# Slave.net
KiCad netlist of a schematic drawn in Altium Designer
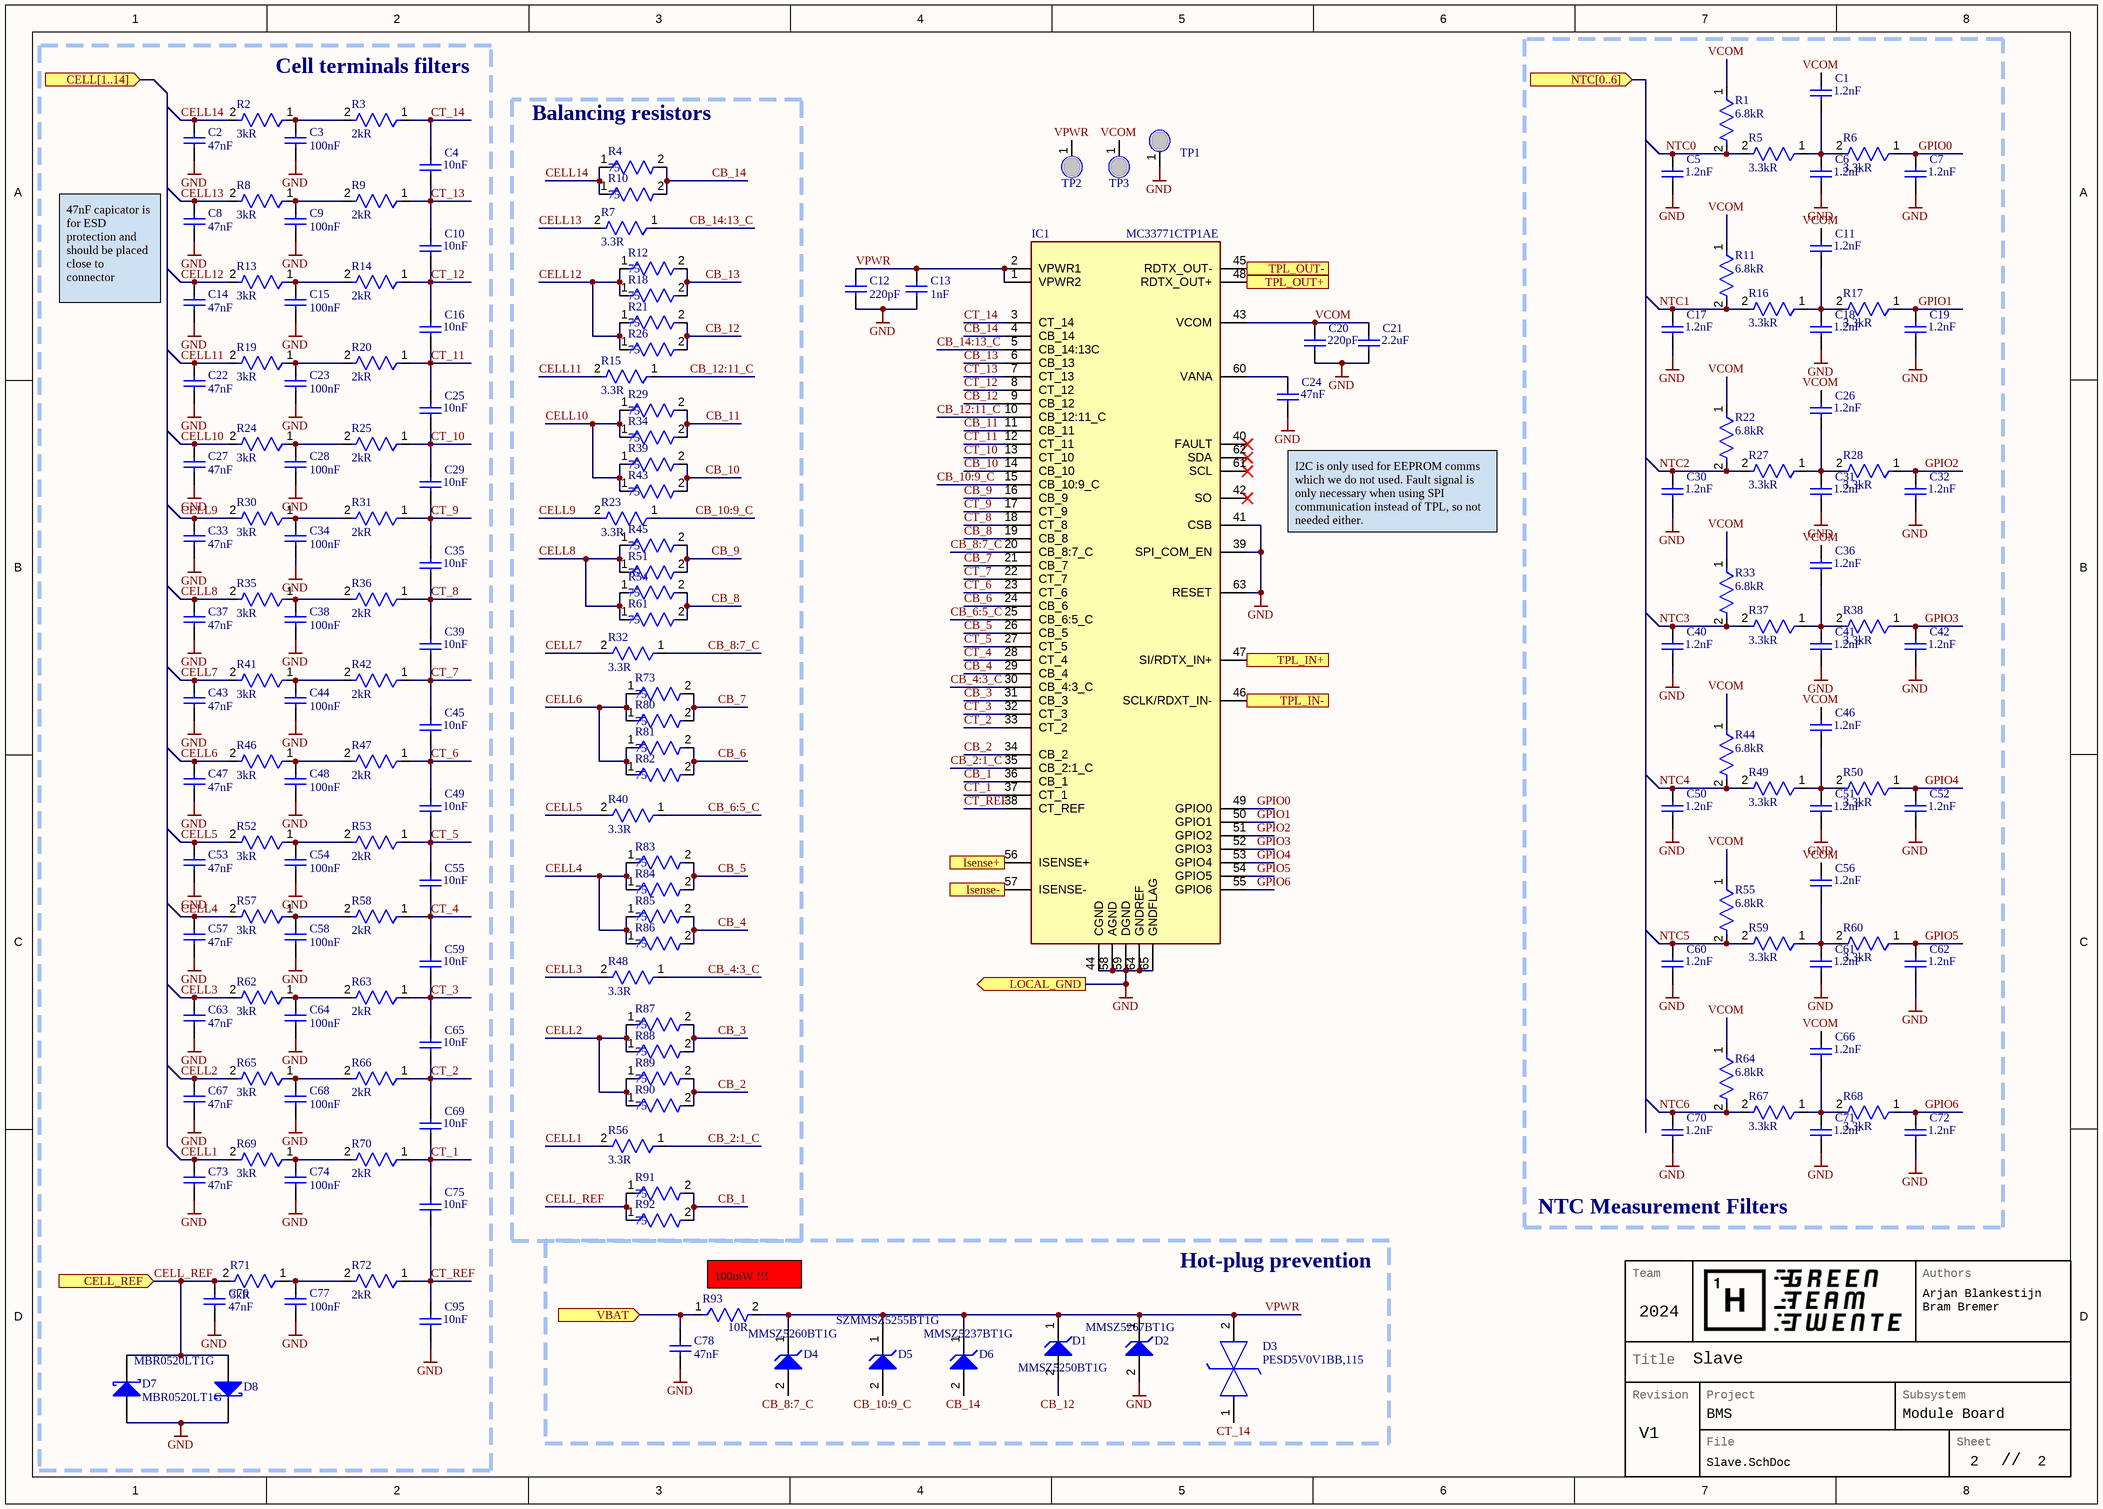
[diagram p0: Slave.SchDoc]

(export (version "E")
  (design (tool "Eeschema 10.0.6"))
  (components
    (comp (ref "C1")
      (value "1.2nF")
      (footprint "WCAP-CSGP_0402_L1W0.5H0.5")
      (description "GTT Standard 0402 non-polarized capacitor")
      (fields (field (name "Comment") "CAP 0402 1.2nF X7R"))
      (libsource (lib "Green Team Twente") (part "CAP_NONPOL_GENERIC"))
    )
    (comp (ref "C2")
      (value "47nF")
      (footprint "WCAP-CSGP_0603_L1.6W0.8H0.8_Reflow")
      (description "GTT Standard 0603 non-polarized capacitor")
      (fields (field (name "TOLERANCE") "5%") (field (name "Comment") "CAP 0603 47nF X7R"))
      (libsource (lib "Green Team Twente") (part "CAP_NONPOL_GENERIC"))
    )
    (comp (ref "C3")
      (value "100nF")
      (footprint "WCAP-CSGP_0603_L1.6W0.8H0.8_Reflow")
      (description "GTT Standard 0603 non-polarized capacitor")
      (fields (field (name "TOLERANCE") "5%") (field (name "Comment") "CAP 0603 100nF X7R"))
      (libsource (lib "Green Team Twente") (part "CAP_NONPOL_GENERIC"))
    )
    (comp (ref "C4")
      (value "10nF")
      (footprint "WCAP-CSGP_0402_L1W0.5H0.5")
      (description "GTT Standard 0402 non-polarized capacitor")
      (fields (field (name "Comment") "CAP 0402 10nF X7R"))
      (libsource (lib "Green Team Twente") (part "CAP_NONPOL_GENERIC"))
    )
    (comp (ref "C5")
      (value "1.2nF")
      (footprint "WCAP-CSGP_0402_L1W0.5H0.5")
      (description "GTT Standard 0402 non-polarized capacitor")
      (fields (field (name "Comment") "CAP 0402 1.2nF X7R"))
      (libsource (lib "Green Team Twente") (part "CAP_NONPOL_GENERIC"))
    )
    (comp (ref "C6")
      (value "1.2nF")
      (footprint "WCAP-CSGP_0402_L1W0.5H0.5")
      (description "GTT Standard 0402 non-polarized capacitor")
      (fields (field (name "Comment") "CAP 0402 1.2nF X7R"))
      (libsource (lib "Green Team Twente") (part "CAP_NONPOL_GENERIC"))
    )
    (comp (ref "C7")
      (value "1.2nF")
      (footprint "WCAP-CSGP_0402_L1W0.5H0.5")
      (description "GTT Standard 0402 non-polarized capacitor")
      (fields (field (name "Comment") "CAP 0402 1.2nF X7R"))
      (libsource (lib "Green Team Twente") (part "CAP_NONPOL_GENERIC"))
    )
    (comp (ref "C8")
      (value "47nF")
      (footprint "WCAP-CSGP_0603_L1.6W0.8H0.8_Reflow")
      (description "GTT Standard 0603 non-polarized capacitor")
      (fields (field (name "TOLERANCE") "5%") (field (name "Comment") "CAP 0603 47nF X7R"))
      (libsource (lib "Green Team Twente") (part "CAP_NONPOL_GENERIC"))
    )
    (comp (ref "C9")
      (value "100nF")
      (footprint "WCAP-CSGP_0603_L1.6W0.8H0.8_Reflow")
      (description "GTT Standard 0603 non-polarized capacitor")
      (fields (field (name "TOLERANCE") "5%") (field (name "Comment") "CAP 0603 100nF X7R"))
      (libsource (lib "Green Team Twente") (part "CAP_NONPOL_GENERIC"))
    )
    (comp (ref "C10")
      (value "10nF")
      (footprint "WCAP-CSGP_0402_L1W0.5H0.5")
      (description "GTT Standard 0402 non-polarized capacitor")
      (fields (field (name "Comment") "CAP 0402 10nF X7R"))
      (libsource (lib "Green Team Twente") (part "CAP_NONPOL_GENERIC"))
    )
    (comp (ref "C11")
      (value "1.2nF")
      (footprint "WCAP-CSGP_0402_L1W0.5H0.5")
      (description "GTT Standard 0402 non-polarized capacitor")
      (fields (field (name "Comment") "CAP 0402 1.2nF X7R"))
      (libsource (lib "Green Team Twente") (part "CAP_NONPOL_GENERIC"))
    )
    (comp (ref "C12")
      (value "220pF")
      (footprint "WCAP-CSGP_0603_L1.6W0.8H0.8_Reflow")
      (description "GTT Standard 0603 non-polarized capacitor")
      (fields (field (name "TOLERANCE") "5%") (field (name "Comment") "CAP 0603 220pF X7R"))
      (libsource (lib "Green Team Twente") (part "CAP_NONPOL_GENERIC"))
    )
    (comp (ref "C13")
      (value "1nF")
      (footprint "WCAP-CSGP_0603_L1.6W0.8H0.8_Reflow")
      (description "GTT Standard 0603 non-polarized capacitor")
      (fields (field (name "TOLERANCE") "5%") (field (name "Comment") "CAP 0603 1nF X7R"))
      (libsource (lib "Green Team Twente") (part "CAP_NONPOL_GENERIC"))
    )
    (comp (ref "C14")
      (value "47nF")
      (footprint "WCAP-CSGP_0603_L1.6W0.8H0.8_Reflow")
      (description "GTT Standard 0603 non-polarized capacitor")
      (fields (field (name "TOLERANCE") "5%") (field (name "Comment") "CAP 0603 47nF X7R"))
      (libsource (lib "Green Team Twente") (part "CAP_NONPOL_GENERIC"))
    )
    (comp (ref "C15")
      (value "100nF")
      (footprint "WCAP-CSGP_0603_L1.6W0.8H0.8_Reflow")
      (description "GTT Standard 0603 non-polarized capacitor")
      (fields (field (name "TOLERANCE") "5%") (field (name "Comment") "CAP 0603 100nF X7R"))
      (libsource (lib "Green Team Twente") (part "CAP_NONPOL_GENERIC"))
    )
    (comp (ref "C16")
      (value "10nF")
      (footprint "WCAP-CSGP_0402_L1W0.5H0.5")
      (description "GTT Standard 0402 non-polarized capacitor")
      (fields (field (name "Comment") "CAP 0402 10nF X7R"))
      (libsource (lib "Green Team Twente") (part "CAP_NONPOL_GENERIC"))
    )
    (comp (ref "C17")
      (value "1.2nF")
      (footprint "WCAP-CSGP_0402_L1W0.5H0.5")
      (description "GTT Standard 0402 non-polarized capacitor")
      (fields (field (name "Comment") "CAP 0402 1.2nF X7R"))
      (libsource (lib "Green Team Twente") (part "CAP_NONPOL_GENERIC"))
    )
    (comp (ref "C18")
      (value "1.2nF")
      (footprint "WCAP-CSGP_0402_L1W0.5H0.5")
      (description "GTT Standard 0402 non-polarized capacitor")
      (fields (field (name "Comment") "CAP 0402 1.2nF X7R"))
      (libsource (lib "Green Team Twente") (part "CAP_NONPOL_GENERIC"))
    )
    (comp (ref "C19")
      (value "1.2nF")
      (footprint "WCAP-CSGP_0402_L1W0.5H0.5")
      (description "GTT Standard 0402 non-polarized capacitor")
      (fields (field (name "Comment") "CAP 0402 1.2nF X7R"))
      (libsource (lib "Green Team Twente") (part "CAP_NONPOL_GENERIC"))
    )
    (comp (ref "C20")
      (value "220pF")
      (footprint "WCAP-CSGP_0402_L1W0.5H0.5")
      (description "GTT Standard 0402 non-polarized capacitor")
      (fields (field (name "Comment") "CAP 0402 220pF X7R"))
      (libsource (lib "Green Team Twente") (part "CAP_NONPOL_GENERIC"))
    )
    (comp (ref "C21")
      (value "2.2uF")
      (footprint "WCAP-CSGP_0402_L1W0.5H0.5")
      (description "GTT Standard 0402 non-polarized capacitor")
      (fields (field (name "Comment") "CAP 0402 2.2uF X7R"))
      (libsource (lib "Green Team Twente") (part "CAP_NONPOL_GENERIC"))
    )
    (comp (ref "C22")
      (value "47nF")
      (footprint "WCAP-CSGP_0603_L1.6W0.8H0.8_Reflow")
      (description "GTT Standard 0603 non-polarized capacitor")
      (fields (field (name "TOLERANCE") "5%") (field (name "Comment") "CAP 0603 47nF X7R"))
      (libsource (lib "Green Team Twente") (part "CAP_NONPOL_GENERIC"))
    )
    (comp (ref "C23")
      (value "100nF")
      (footprint "WCAP-CSGP_0603_L1.6W0.8H0.8_Reflow")
      (description "GTT Standard 0603 non-polarized capacitor")
      (fields (field (name "TOLERANCE") "5%") (field (name "Comment") "CAP 0603 100nF X7R"))
      (libsource (lib "Green Team Twente") (part "CAP_NONPOL_GENERIC"))
    )
    (comp (ref "C24")
      (value "47nF")
      (footprint "WCAP-CSGP_0402_L1W0.5H0.5")
      (description "GTT Standard 0402 non-polarized capacitor")
      (fields (field (name "Comment") "CAP 0402 47nF X7R"))
      (libsource (lib "Green Team Twente") (part "CAP_NONPOL_GENERIC"))
    )
    (comp (ref "C25")
      (value "10nF")
      (footprint "WCAP-CSGP_0402_L1W0.5H0.5")
      (description "GTT Standard 0402 non-polarized capacitor")
      (fields (field (name "Comment") "CAP 0402 10nF X7R"))
      (libsource (lib "Green Team Twente") (part "CAP_NONPOL_GENERIC"))
    )
    (comp (ref "C26")
      (value "1.2nF")
      (footprint "WCAP-CSGP_0402_L1W0.5H0.5")
      (description "GTT Standard 0402 non-polarized capacitor")
      (fields (field (name "Comment") "CAP 0402 1.2nF X7R"))
      (libsource (lib "Green Team Twente") (part "CAP_NONPOL_GENERIC"))
    )
    (comp (ref "C27")
      (value "47nF")
      (footprint "WCAP-CSGP_0603_L1.6W0.8H0.8_Reflow")
      (description "GTT Standard 0603 non-polarized capacitor")
      (fields (field (name "TOLERANCE") "5%") (field (name "Comment") "CAP 0603 47nF X7R"))
      (libsource (lib "Green Team Twente") (part "CAP_NONPOL_GENERIC"))
    )
    (comp (ref "C28")
      (value "100nF")
      (footprint "WCAP-CSGP_0603_L1.6W0.8H0.8_Reflow")
      (description "GTT Standard 0603 non-polarized capacitor")
      (fields (field (name "TOLERANCE") "5%") (field (name "Comment") "CAP 0603 100nF X7R"))
      (libsource (lib "Green Team Twente") (part "CAP_NONPOL_GENERIC"))
    )
    (comp (ref "C29")
      (value "10nF")
      (footprint "WCAP-CSGP_0402_L1W0.5H0.5")
      (description "GTT Standard 0402 non-polarized capacitor")
      (fields (field (name "Comment") "CAP 0402 10nF X7R"))
      (libsource (lib "Green Team Twente") (part "CAP_NONPOL_GENERIC"))
    )
    (comp (ref "C30")
      (value "1.2nF")
      (footprint "WCAP-CSGP_0402_L1W0.5H0.5")
      (description "GTT Standard 0402 non-polarized capacitor")
      (fields (field (name "Comment") "CAP 0402 1.2nF X7R"))
      (libsource (lib "Green Team Twente") (part "CAP_NONPOL_GENERIC"))
    )
    (comp (ref "C31")
      (value "1.2nF")
      (footprint "WCAP-CSGP_0402_L1W0.5H0.5")
      (description "GTT Standard 0402 non-polarized capacitor")
      (fields (field (name "Comment") "CAP 0402 1.2nF X7R"))
      (libsource (lib "Green Team Twente") (part "CAP_NONPOL_GENERIC"))
    )
    (comp (ref "C32")
      (value "1.2nF")
      (footprint "WCAP-CSGP_0402_L1W0.5H0.5")
      (description "GTT Standard 0402 non-polarized capacitor")
      (fields (field (name "Comment") "CAP 0402 1.2nF X7R"))
      (libsource (lib "Green Team Twente") (part "CAP_NONPOL_GENERIC"))
    )
    (comp (ref "C33")
      (value "47nF")
      (footprint "WCAP-CSGP_0603_L1.6W0.8H0.8_Reflow")
      (description "GTT Standard 0603 non-polarized capacitor")
      (fields (field (name "TOLERANCE") "5%") (field (name "Comment") "CAP 0603 47nF X7R"))
      (libsource (lib "Green Team Twente") (part "CAP_NONPOL_GENERIC"))
    )
    (comp (ref "C34")
      (value "100nF")
      (footprint "WCAP-CSGP_0603_L1.6W0.8H0.8_Reflow")
      (description "GTT Standard 0603 non-polarized capacitor")
      (fields (field (name "TOLERANCE") "5%") (field (name "Comment") "CAP 0603 100nF X7R"))
      (libsource (lib "Green Team Twente") (part "CAP_NONPOL_GENERIC"))
    )
    (comp (ref "C35")
      (value "10nF")
      (footprint "WCAP-CSGP_0402_L1W0.5H0.5")
      (description "GTT Standard 0402 non-polarized capacitor")
      (fields (field (name "Comment") "CAP 0402 10nF X7R"))
      (libsource (lib "Green Team Twente") (part "CAP_NONPOL_GENERIC"))
    )
    (comp (ref "C36")
      (value "1.2nF")
      (footprint "WCAP-CSGP_0402_L1W0.5H0.5")
      (description "GTT Standard 0402 non-polarized capacitor")
      (fields (field (name "Comment") "CAP 0402 1.2nF X7R"))
      (libsource (lib "Green Team Twente") (part "CAP_NONPOL_GENERIC"))
    )
    (comp (ref "C37")
      (value "47nF")
      (footprint "WCAP-CSGP_0603_L1.6W0.8H0.8_Reflow")
      (description "GTT Standard 0603 non-polarized capacitor")
      (fields (field (name "TOLERANCE") "5%") (field (name "Comment") "CAP 0603 47nF X7R"))
      (libsource (lib "Green Team Twente") (part "CAP_NONPOL_GENERIC"))
    )
    (comp (ref "C38")
      (value "100nF")
      (footprint "WCAP-CSGP_0603_L1.6W0.8H0.8_Reflow")
      (description "GTT Standard 0603 non-polarized capacitor")
      (fields (field (name "TOLERANCE") "5%") (field (name "Comment") "CAP 0603 100nF X7R"))
      (libsource (lib "Green Team Twente") (part "CAP_NONPOL_GENERIC"))
    )
    (comp (ref "C39")
      (value "10nF")
      (footprint "WCAP-CSGP_0402_L1W0.5H0.5")
      (description "GTT Standard 0402 non-polarized capacitor")
      (fields (field (name "Comment") "CAP 0402 10nF X7R"))
      (libsource (lib "Green Team Twente") (part "CAP_NONPOL_GENERIC"))
    )
    (comp (ref "C40")
      (value "1.2nF")
      (footprint "WCAP-CSGP_0402_L1W0.5H0.5")
      (description "GTT Standard 0402 non-polarized capacitor")
      (fields (field (name "Comment") "CAP 0402 1.2nF X7R"))
      (libsource (lib "Green Team Twente") (part "CAP_NONPOL_GENERIC"))
    )
    (comp (ref "C41")
      (value "1.2nF")
      (footprint "WCAP-CSGP_0402_L1W0.5H0.5")
      (description "GTT Standard 0402 non-polarized capacitor")
      (fields (field (name "Comment") "CAP 0402 1.2nF X7R"))
      (libsource (lib "Green Team Twente") (part "CAP_NONPOL_GENERIC"))
    )
    (comp (ref "C42")
      (value "1.2nF")
      (footprint "WCAP-CSGP_0402_L1W0.5H0.5")
      (description "GTT Standard 0402 non-polarized capacitor")
      (fields (field (name "Comment") "CAP 0402 1.2nF X7R"))
      (libsource (lib "Green Team Twente") (part "CAP_NONPOL_GENERIC"))
    )
    (comp (ref "C43")
      (value "47nF")
      (footprint "WCAP-CSGP_0603_L1.6W0.8H0.8_Reflow")
      (description "GTT Standard 0603 non-polarized capacitor")
      (fields (field (name "TOLERANCE") "5%") (field (name "Comment") "CAP 0603 47nF X7R"))
      (libsource (lib "Green Team Twente") (part "CAP_NONPOL_GENERIC"))
    )
    (comp (ref "C44")
      (value "100nF")
      (footprint "WCAP-CSGP_0603_L1.6W0.8H0.8_Reflow")
      (description "GTT Standard 0603 non-polarized capacitor")
      (fields (field (name "TOLERANCE") "5%") (field (name "Comment") "CAP 0603 100nF X7R"))
      (libsource (lib "Green Team Twente") (part "CAP_NONPOL_GENERIC"))
    )
    (comp (ref "C45")
      (value "10nF")
      (footprint "WCAP-CSGP_0402_L1W0.5H0.5")
      (description "GTT Standard 0402 non-polarized capacitor")
      (fields (field (name "Comment") "CAP 0402 10nF X7R"))
      (libsource (lib "Green Team Twente") (part "CAP_NONPOL_GENERIC"))
    )
    (comp (ref "C46")
      (value "1.2nF")
      (footprint "WCAP-CSGP_0402_L1W0.5H0.5")
      (description "GTT Standard 0402 non-polarized capacitor")
      (fields (field (name "Comment") "CAP 0402 1.2nF X7R"))
      (libsource (lib "Green Team Twente") (part "CAP_NONPOL_GENERIC"))
    )
    (comp (ref "C47")
      (value "47nF")
      (footprint "WCAP-CSGP_0603_L1.6W0.8H0.8_Reflow")
      (description "GTT Standard 0603 non-polarized capacitor")
      (fields (field (name "TOLERANCE") "5%") (field (name "Comment") "CAP 0603 47nF X7R"))
      (libsource (lib "Green Team Twente") (part "CAP_NONPOL_GENERIC"))
    )
    (comp (ref "C48")
      (value "100nF")
      (footprint "WCAP-CSGP_0603_L1.6W0.8H0.8_Reflow")
      (description "GTT Standard 0603 non-polarized capacitor")
      (fields (field (name "TOLERANCE") "5%") (field (name "Comment") "CAP 0603 100nF X7R"))
      (libsource (lib "Green Team Twente") (part "CAP_NONPOL_GENERIC"))
    )
    (comp (ref "C49")
      (value "10nF")
      (footprint "WCAP-CSGP_0402_L1W0.5H0.5")
      (description "GTT Standard 0402 non-polarized capacitor")
      (fields (field (name "Comment") "CAP 0402 10nF X7R"))
      (libsource (lib "Green Team Twente") (part "CAP_NONPOL_GENERIC"))
    )
    (comp (ref "C50")
      (value "1.2nF")
      (footprint "WCAP-CSGP_0402_L1W0.5H0.5")
      (description "GTT Standard 0402 non-polarized capacitor")
      (fields (field (name "Comment") "CAP 0402 1.2nF X7R"))
      (libsource (lib "Green Team Twente") (part "CAP_NONPOL_GENERIC"))
    )
    (comp (ref "C51")
      (value "1.2nF")
      (footprint "WCAP-CSGP_0402_L1W0.5H0.5")
      (description "GTT Standard 0402 non-polarized capacitor")
      (fields (field (name "Comment") "CAP 0402 1.2nF X7R"))
      (libsource (lib "Green Team Twente") (part "CAP_NONPOL_GENERIC"))
    )
    (comp (ref "C52")
      (value "1.2nF")
      (footprint "WCAP-CSGP_0402_L1W0.5H0.5")
      (description "GTT Standard 0402 non-polarized capacitor")
      (fields (field (name "Comment") "CAP 0402 1.2nF X7R"))
      (libsource (lib "Green Team Twente") (part "CAP_NONPOL_GENERIC"))
    )
    (comp (ref "C53")
      (value "47nF")
      (footprint "WCAP-CSGP_0603_L1.6W0.8H0.8_Reflow")
      (description "GTT Standard 0603 non-polarized capacitor")
      (fields (field (name "TOLERANCE") "5%") (field (name "Comment") "CAP 0603 47nF X7R"))
      (libsource (lib "Green Team Twente") (part "CAP_NONPOL_GENERIC"))
    )
    (comp (ref "C54")
      (value "100nF")
      (footprint "WCAP-CSGP_0603_L1.6W0.8H0.8_Reflow")
      (description "GTT Standard 0603 non-polarized capacitor")
      (fields (field (name "TOLERANCE") "5%") (field (name "Comment") "CAP 0603 100nF X7R"))
      (libsource (lib "Green Team Twente") (part "CAP_NONPOL_GENERIC"))
    )
    (comp (ref "C55")
      (value "10nF")
      (footprint "WCAP-CSGP_0402_L1W0.5H0.5")
      (description "GTT Standard 0402 non-polarized capacitor")
      (fields (field (name "Comment") "CAP 0402 10nF X7R"))
      (libsource (lib "Green Team Twente") (part "CAP_NONPOL_GENERIC"))
    )
    (comp (ref "C56")
      (value "1.2nF")
      (footprint "WCAP-CSGP_0402_L1W0.5H0.5")
      (description "GTT Standard 0402 non-polarized capacitor")
      (fields (field (name "Comment") "CAP 0402 1.2nF X7R"))
      (libsource (lib "Green Team Twente") (part "CAP_NONPOL_GENERIC"))
    )
    (comp (ref "C57")
      (value "47nF")
      (footprint "WCAP-CSGP_0603_L1.6W0.8H0.8_Reflow")
      (description "GTT Standard 0603 non-polarized capacitor")
      (fields (field (name "TOLERANCE") "5%") (field (name "Comment") "CAP 0603 47nF X7R"))
      (libsource (lib "Green Team Twente") (part "CAP_NONPOL_GENERIC"))
    )
    (comp (ref "C58")
      (value "100nF")
      (footprint "WCAP-CSGP_0603_L1.6W0.8H0.8_Reflow")
      (description "GTT Standard 0603 non-polarized capacitor")
      (fields (field (name "TOLERANCE") "5%") (field (name "Comment") "CAP 0603 100nF X7R"))
      (libsource (lib "Green Team Twente") (part "CAP_NONPOL_GENERIC"))
    )
    (comp (ref "C59")
      (value "10nF")
      (footprint "WCAP-CSGP_0402_L1W0.5H0.5")
      (description "GTT Standard 0402 non-polarized capacitor")
      (fields (field (name "Comment") "CAP 0402 10nF X7R"))
      (libsource (lib "Green Team Twente") (part "CAP_NONPOL_GENERIC"))
    )
    (comp (ref "C60")
      (value "1.2nF")
      (footprint "WCAP-CSGP_0402_L1W0.5H0.5")
      (description "GTT Standard 0402 non-polarized capacitor")
      (fields (field (name "Comment") "CAP 0402 1.2nF X7R"))
      (libsource (lib "Green Team Twente") (part "CAP_NONPOL_GENERIC"))
    )
    (comp (ref "C61")
      (value "1.2nF")
      (footprint "WCAP-CSGP_0402_L1W0.5H0.5")
      (description "GTT Standard 0402 non-polarized capacitor")
      (fields (field (name "Comment") "CAP 0402 1.2nF X7R"))
      (libsource (lib "Green Team Twente") (part "CAP_NONPOL_GENERIC"))
    )
    (comp (ref "C62")
      (value "1.2nF")
      (footprint "WCAP-CSGP_0402_L1W0.5H0.5")
      (description "GTT Standard 0402 non-polarized capacitor")
      (fields (field (name "Comment") "CAP 0402 1.2nF X7R"))
      (libsource (lib "Green Team Twente") (part "CAP_NONPOL_GENERIC"))
    )
    (comp (ref "C63")
      (value "47nF")
      (footprint "WCAP-CSGP_0603_L1.6W0.8H0.8_Reflow")
      (description "GTT Standard 0603 non-polarized capacitor")
      (fields (field (name "TOLERANCE") "5%") (field (name "Comment") "CAP 0603 47nF X7R"))
      (libsource (lib "Green Team Twente") (part "CAP_NONPOL_GENERIC"))
    )
    (comp (ref "C64")
      (value "100nF")
      (footprint "WCAP-CSGP_0603_L1.6W0.8H0.8_Reflow")
      (description "GTT Standard 0603 non-polarized capacitor")
      (fields (field (name "TOLERANCE") "5%") (field (name "Comment") "CAP 0603 100nF X7R"))
      (libsource (lib "Green Team Twente") (part "CAP_NONPOL_GENERIC"))
    )
    (comp (ref "C65")
      (value "10nF")
      (footprint "WCAP-CSGP_0402_L1W0.5H0.5")
      (description "GTT Standard 0402 non-polarized capacitor")
      (fields (field (name "Comment") "CAP 0402 10nF X7R"))
      (libsource (lib "Green Team Twente") (part "CAP_NONPOL_GENERIC"))
    )
    (comp (ref "C66")
      (value "1.2nF")
      (footprint "WCAP-CSGP_0402_L1W0.5H0.5")
      (description "GTT Standard 0402 non-polarized capacitor")
      (fields (field (name "Comment") "CAP 0402 1.2nF X7R"))
      (libsource (lib "Green Team Twente") (part "CAP_NONPOL_GENERIC"))
    )
    (comp (ref "C67")
      (value "47nF")
      (footprint "WCAP-CSGP_0603_L1.6W0.8H0.8_Reflow")
      (description "GTT Standard 0603 non-polarized capacitor")
      (fields (field (name "TOLERANCE") "5%") (field (name "Comment") "CAP 0603 47nF X7R"))
      (libsource (lib "Green Team Twente") (part "CAP_NONPOL_GENERIC"))
    )
    (comp (ref "C68")
      (value "100nF")
      (footprint "WCAP-CSGP_0603_L1.6W0.8H0.8_Reflow")
      (description "GTT Standard 0603 non-polarized capacitor")
      (fields (field (name "TOLERANCE") "5%") (field (name "Comment") "CAP 0603 100nF X7R"))
      (libsource (lib "Green Team Twente") (part "CAP_NONPOL_GENERIC"))
    )
    (comp (ref "C69")
      (value "10nF")
      (footprint "WCAP-CSGP_0402_L1W0.5H0.5")
      (description "GTT Standard 0402 non-polarized capacitor")
      (fields (field (name "Comment") "CAP 0402 10nF X7R"))
      (libsource (lib "Green Team Twente") (part "CAP_NONPOL_GENERIC"))
    )
    (comp (ref "C70")
      (value "1.2nF")
      (footprint "WCAP-CSGP_0402_L1W0.5H0.5")
      (description "GTT Standard 0402 non-polarized capacitor")
      (fields (field (name "Comment") "CAP 0402 1.2nF X7R"))
      (libsource (lib "Green Team Twente") (part "CAP_NONPOL_GENERIC"))
    )
    (comp (ref "C71")
      (value "1.2nF")
      (footprint "WCAP-CSGP_0402_L1W0.5H0.5")
      (description "GTT Standard 0402 non-polarized capacitor")
      (fields (field (name "Comment") "CAP 0402 1.2nF X7R"))
      (libsource (lib "Green Team Twente") (part "CAP_NONPOL_GENERIC"))
    )
    (comp (ref "C72")
      (value "1.2nF")
      (footprint "WCAP-CSGP_0402_L1W0.5H0.5")
      (description "GTT Standard 0402 non-polarized capacitor")
      (fields (field (name "Comment") "CAP 0402 1.2nF X7R"))
      (libsource (lib "Green Team Twente") (part "CAP_NONPOL_GENERIC"))
    )
    (comp (ref "C73")
      (value "47nF")
      (footprint "WCAP-CSGP_0603_L1.6W0.8H0.8_Reflow")
      (description "GTT Standard 0603 non-polarized capacitor")
      (fields (field (name "TOLERANCE") "5%") (field (name "Comment") "CAP 0603 47nF X7R"))
      (libsource (lib "Green Team Twente") (part "CAP_NONPOL_GENERIC"))
    )
    (comp (ref "C74")
      (value "100nF")
      (footprint "WCAP-CSGP_0603_L1.6W0.8H0.8_Reflow")
      (description "GTT Standard 0603 non-polarized capacitor")
      (fields (field (name "TOLERANCE") "5%") (field (name "Comment") "CAP 0603 100nF X7R"))
      (libsource (lib "Green Team Twente") (part "CAP_NONPOL_GENERIC"))
    )
    (comp (ref "C75")
      (value "10nF")
      (footprint "WCAP-CSGP_0402_L1W0.5H0.5")
      (description "GTT Standard 0402 non-polarized capacitor")
      (fields (field (name "Comment") "CAP 0402 10nF X7R"))
      (libsource (lib "Green Team Twente") (part "CAP_NONPOL_GENERIC"))
    )
    (comp (ref "C76")
      (value "47nF")
      (footprint "WCAP-CSGP_0603_L1.6W0.8H0.8_Reflow")
      (description "GTT Standard 0603 non-polarized capacitor")
      (fields (field (name "TOLERANCE") "5%") (field (name "Comment") "CAP 0603 47nF X7R"))
      (libsource (lib "Green Team Twente") (part "CAP_NONPOL_GENERIC"))
    )
    (comp (ref "C77")
      (value "100nF")
      (footprint "WCAP-CSGP_0603_L1.6W0.8H0.8_Reflow")
      (description "GTT Standard 0603 non-polarized capacitor")
      (fields (field (name "TOLERANCE") "5%") (field (name "Comment") "CAP 0603 100nF X7R"))
      (libsource (lib "Green Team Twente") (part "CAP_NONPOL_GENERIC"))
    )
    (comp (ref "C78")
      (value "47nF")
      (footprint "WCAP-CSGP_0603_L1.6W0.8H0.8_Reflow")
      (description "GTT Standard 0603 non-polarized capacitor")
      (fields (field (name "TOLERANCE") "5%") (field (name "Comment") "CAP 0603 47nF X7R"))
      (libsource (lib "Green Team Twente") (part "CAP_NONPOL_GENERIC"))
    )
    (comp (ref "C95")
      (value "10nF")
      (footprint "WCAP-CSGP_0402_L1W0.5H0.5")
      (description "GTT Standard 0402 non-polarized capacitor")
      (fields (field (name "Comment") "CAP 0402 10nF X7R"))
      (libsource (lib "Green Team Twente") (part "CAP_NONPOL_GENERIC"))
    )
    (comp (ref "D1")
      (value "MMSZ5250BT1G")
      (footprint "ONSC-SOD-123-2-425-04_V")
      (description "Zener Voltage Regulator, 500 mW, 2-Pin SOD-123, Pb-Free, Tape and Reel")
      (fields (field (name "MANUFACTURER") "On Semiconductor"))
      (libsource (lib "Altium Content Vault") (part "ONSC-K1A2-2"))
    )
    (comp (ref "D2")
      (value "MMSZ5267BT1G")
      (footprint "ONSC-SOD-123-2-425-04_V")
      (description "Zener Voltage Regulator, 500 mW, 2-Pin SOD-123, Pb-Free, Tape and Reel")
      (fields (field (name "MANUFACTURER") "On Semiconductor"))
      (libsource (lib "Altium Content Vault") (part "ONSC-K1A2-2"))
    )
    (comp (ref "D3")
      (value "PESD5V0V1BB,115")
      (footprint "PESD5V0V1BB115")
      (description "PESD5V0V1BB - Very low capacitance bidirectional ESD protection diode")
      (fields (field (name "MOUSER PART NUMBER") "771-PESD5V0V1BB115"))
      (libsource (lib "Green Team Twente") (part "PESD5V0V1BB,115"))
    )
    (comp (ref "D4")
      (value "MMSZ5260BT1G")
      (footprint "ONSC-SOD-123-2-425-04_V")
      (description "Zener Voltage Regulator, 500 mW, 2-Pin SOD-123, Pb-Free, Tape and Reel")
      (fields (field (name "MANUFACTURER") "On Semiconductor"))
      (libsource (lib "Altium Content Vault") (part "ONSC-K1A2-2"))
    )
    (comp (ref "D5")
      (value "SZMMSZ5255BT1G")
      (footprint "ONSC-SOD-123-2-425-04_V")
      (description "Zener Voltage Regulator, 500 mW, 2-Pin SOD-123, Pb-Free, Tape and Reel")
      (fields (field (name "MANUFACTURER") "On Semiconductor"))
      (libsource (lib "Altium Content Vault") (part "ONSC-K1A2-2"))
    )
    (comp (ref "D6")
      (value "MMSZ5237BT1G")
      (footprint "ONSC-SOD-123-2-425-04_V")
      (description "Zener Voltage Regulator, 500 mW, 2-Pin SOD-123, Pb-Free, Tape and Reel")
      (fields (field (name "MANUFACTURER") "On Semiconductor"))
      (libsource (lib "Altium Content Vault") (part "ONSC-K1A2-2"))
    )
    (comp (ref "D7")
      (value "MBR0520LT1G")
      (footprint "ONSC-SOD-123-2-425-04_V")
      (description "Schottky Power Rectifier, 20 V, 5.5 A, -65 to 125 degC, 2-Pin SMD, RoHS, Tape and Reel")
      (fields (field (name "MANUFACTURER") "ON Semiconductor"))
      (libsource (lib "Green Team Twente") (part "DSKY-AK-2"))
    )
    (comp (ref "D8")
      (value "MBR0520LT1G")
      (footprint "ONSC-SOD-123-2-425-04_V")
      (description "Schottky Power Rectifier, 20 V, 5.5 A, -65 to 125 degC, 2-Pin SMD, RoHS, Tape and Reel")
      (fields (field (name "MANUFACTURER") "ON Semiconductor"))
      (libsource (lib "Green Team Twente") (part "DSKY-AK-2"))
    )
    (comp (ref "IC1")
      (value "MC33771CTP1AE")
      (footprint "QFP50P1200X1200X160-65N")
      (description "Integrated Circuit")
      (fields (field (name "MOUSER PART NUMBER") "771-MC33771CTP1AE"))
      (libsource (lib "Green Team Twente") (part "MC33771CTP1AE"))
    )
    (comp (ref "R1")
      (value "6.8kR")
      (footprint "FP0402")
      (description "GTT Standard 0402 Resistor")
      (fields (field (name "TOLERANCE") "1%") (field (name "POWER") "62.5mW"))
      (libsource (lib "Green Team Twente") (part "RES_GENERIC"))
    )
    (comp (ref "R2")
      (value "3kR")
      (footprint "FP0402")
      (description "GTT Standard 0402 Resistor")
      (fields (field (name "TOLERANCE") "1%") (field (name "POWER") "62.5mW"))
      (libsource (lib "Green Team Twente") (part "RES_GENERIC"))
    )
    (comp (ref "R3")
      (value "2kR")
      (footprint "FP0402")
      (description "GTT Standard 0402 Resistor")
      (fields (field (name "TOLERANCE") "1%") (field (name "POWER") "62.5mW"))
      (libsource (lib "Green Team Twente") (part "RES_GENERIC"))
    )
    (comp (ref "R4")
      (value "75")
      (footprint "RES_SM1206_YAGEORC_N")
      (description "GTT Standard 1206 Resistor")
      (fields (field (name "TOLERANCE") "1%") (field (name "POWER") "250mW"))
      (libsource (lib "Green Team Twente") (part "RES_GENERIC"))
    )
    (comp (ref "R5")
      (value "3.3kR")
      (footprint "FP0402")
      (description "GTT Standard 0402 Resistor")
      (fields (field (name "TOLERANCE") "1%") (field (name "POWER") "62.5mW"))
      (libsource (lib "Green Team Twente") (part "RES_GENERIC"))
    )
    (comp (ref "R6")
      (value "3.3kR")
      (footprint "FP0402")
      (description "GTT Standard 0402 Resistor")
      (fields (field (name "TOLERANCE") "1%") (field (name "POWER") "62.5mW"))
      (libsource (lib "Green Team Twente") (part "RES_GENERIC"))
    )
    (comp (ref "R7")
      (value "3.3R")
      (footprint "FP0402")
      (description "GTT Standard 0402 Resistor")
      (fields (field (name "TOLERANCE") "1%") (field (name "POWER") "62.5mW"))
      (libsource (lib "Green Team Twente") (part "RES_GENERIC"))
    )
    (comp (ref "R8")
      (value "3kR")
      (footprint "FP0402")
      (description "GTT Standard 0402 Resistor")
      (fields (field (name "TOLERANCE") "1%") (field (name "POWER") "62.5mW"))
      (libsource (lib "Green Team Twente") (part "RES_GENERIC"))
    )
    (comp (ref "R9")
      (value "2kR")
      (footprint "FP0402")
      (description "GTT Standard 0402 Resistor")
      (fields (field (name "TOLERANCE") "1%") (field (name "POWER") "62.5mW"))
      (libsource (lib "Green Team Twente") (part "RES_GENERIC"))
    )
    (comp (ref "R10")
      (value "75")
      (footprint "RES_SM1206_YAGEORC_N")
      (description "GTT Standard 1206 Resistor")
      (fields (field (name "TOLERANCE") "1%") (field (name "POWER") "250mW"))
      (libsource (lib "Green Team Twente") (part "RES_GENERIC"))
    )
    (comp (ref "R11")
      (value "6.8kR")
      (footprint "FP0402")
      (description "GTT Standard 0402 Resistor")
      (fields (field (name "TOLERANCE") "1%") (field (name "POWER") "62.5mW"))
      (libsource (lib "Green Team Twente") (part "RES_GENERIC"))
    )
    (comp (ref "R12")
      (value "75")
      (footprint "RES_SM1206_YAGEORC_N")
      (description "GTT Standard 1206 Resistor")
      (fields (field (name "TOLERANCE") "1%") (field (name "POWER") "250mW"))
      (libsource (lib "Green Team Twente") (part "RES_GENERIC"))
    )
    (comp (ref "R13")
      (value "3kR")
      (footprint "FP0402")
      (description "GTT Standard 0402 Resistor")
      (fields (field (name "TOLERANCE") "1%") (field (name "POWER") "62.5mW"))
      (libsource (lib "Green Team Twente") (part "RES_GENERIC"))
    )
    (comp (ref "R14")
      (value "2kR")
      (footprint "FP0402")
      (description "GTT Standard 0402 Resistor")
      (fields (field (name "TOLERANCE") "1%") (field (name "POWER") "62.5mW"))
      (libsource (lib "Green Team Twente") (part "RES_GENERIC"))
    )
    (comp (ref "R15")
      (value "3.3R")
      (footprint "FP0402")
      (description "GTT Standard 0402 Resistor")
      (fields (field (name "TOLERANCE") "1%") (field (name "POWER") "62.5mW"))
      (libsource (lib "Green Team Twente") (part "RES_GENERIC"))
    )
    (comp (ref "R16")
      (value "3.3kR")
      (footprint "FP0402")
      (description "GTT Standard 0402 Resistor")
      (fields (field (name "TOLERANCE") "1%") (field (name "POWER") "62.5mW"))
      (libsource (lib "Green Team Twente") (part "RES_GENERIC"))
    )
    (comp (ref "R17")
      (value "3.3kR")
      (footprint "FP0402")
      (description "GTT Standard 0402 Resistor")
      (fields (field (name "TOLERANCE") "1%") (field (name "POWER") "62.5mW"))
      (libsource (lib "Green Team Twente") (part "RES_GENERIC"))
    )
    (comp (ref "R18")
      (value "75")
      (footprint "RES_SM1206_YAGEORC_N")
      (description "GTT Standard 1206 Resistor")
      (fields (field (name "TOLERANCE") "1%") (field (name "POWER") "250mW"))
      (libsource (lib "Green Team Twente") (part "RES_GENERIC"))
    )
    (comp (ref "R19")
      (value "3kR")
      (footprint "FP0402")
      (description "GTT Standard 0402 Resistor")
      (fields (field (name "TOLERANCE") "1%") (field (name "POWER") "62.5mW"))
      (libsource (lib "Green Team Twente") (part "RES_GENERIC"))
    )
    (comp (ref "R20")
      (value "2kR")
      (footprint "FP0402")
      (description "GTT Standard 0402 Resistor")
      (fields (field (name "TOLERANCE") "1%") (field (name "POWER") "62.5mW"))
      (libsource (lib "Green Team Twente") (part "RES_GENERIC"))
    )
    (comp (ref "R21")
      (value "75")
      (footprint "RES_SM1206_YAGEORC_N")
      (description "GTT Standard 1206 Resistor")
      (fields (field (name "TOLERANCE") "1%") (field (name "POWER") "250mW"))
      (libsource (lib "Green Team Twente") (part "RES_GENERIC"))
    )
    (comp (ref "R22")
      (value "6.8kR")
      (footprint "FP0402")
      (description "GTT Standard 0402 Resistor")
      (fields (field (name "TOLERANCE") "1%") (field (name "POWER") "62.5mW"))
      (libsource (lib "Green Team Twente") (part "RES_GENERIC"))
    )
    (comp (ref "R23")
      (value "3.3R")
      (footprint "FP0402")
      (description "GTT Standard 0402 Resistor")
      (fields (field (name "TOLERANCE") "1%") (field (name "POWER") "62.5mW"))
      (libsource (lib "Green Team Twente") (part "RES_GENERIC"))
    )
    (comp (ref "R24")
      (value "3kR")
      (footprint "FP0402")
      (description "GTT Standard 0402 Resistor")
      (fields (field (name "TOLERANCE") "1%") (field (name "POWER") "62.5mW"))
      (libsource (lib "Green Team Twente") (part "RES_GENERIC"))
    )
    (comp (ref "R25")
      (value "2kR")
      (footprint "FP0402")
      (description "GTT Standard 0402 Resistor")
      (fields (field (name "TOLERANCE") "1%") (field (name "POWER") "62.5mW"))
      (libsource (lib "Green Team Twente") (part "RES_GENERIC"))
    )
    (comp (ref "R26")
      (value "75")
      (footprint "RES_SM1206_YAGEORC_N")
      (description "GTT Standard 1206 Resistor")
      (fields (field (name "TOLERANCE") "1%") (field (name "POWER") "250mW"))
      (libsource (lib "Green Team Twente") (part "RES_GENERIC"))
    )
    (comp (ref "R27")
      (value "3.3kR")
      (footprint "FP0402")
      (description "GTT Standard 0402 Resistor")
      (fields (field (name "TOLERANCE") "1%") (field (name "POWER") "62.5mW"))
      (libsource (lib "Green Team Twente") (part "RES_GENERIC"))
    )
    (comp (ref "R28")
      (value "3.3kR")
      (footprint "FP0402")
      (description "GTT Standard 0402 Resistor")
      (fields (field (name "TOLERANCE") "1%") (field (name "POWER") "62.5mW"))
      (libsource (lib "Green Team Twente") (part "RES_GENERIC"))
    )
    (comp (ref "R29")
      (value "75")
      (footprint "RES_SM1206_YAGEORC_N")
      (description "GTT Standard 1206 Resistor")
      (fields (field (name "TOLERANCE") "1%") (field (name "POWER") "250mW"))
      (libsource (lib "Green Team Twente") (part "RES_GENERIC"))
    )
    (comp (ref "R30")
      (value "3kR")
      (footprint "FP0402")
      (description "GTT Standard 0402 Resistor")
      (fields (field (name "TOLERANCE") "1%") (field (name "POWER") "62.5mW"))
      (libsource (lib "Green Team Twente") (part "RES_GENERIC"))
    )
    (comp (ref "R31")
      (value "2kR")
      (footprint "FP0402")
      (description "GTT Standard 0402 Resistor")
      (fields (field (name "TOLERANCE") "1%") (field (name "POWER") "62.5mW"))
      (libsource (lib "Green Team Twente") (part "RES_GENERIC"))
    )
    (comp (ref "R32")
      (value "3.3R")
      (footprint "FP0402")
      (description "GTT Standard 0402 Resistor")
      (fields (field (name "TOLERANCE") "1%") (field (name "POWER") "62.5mW"))
      (libsource (lib "Green Team Twente") (part "RES_GENERIC"))
    )
    (comp (ref "R33")
      (value "6.8kR")
      (footprint "FP0402")
      (description "GTT Standard 0402 Resistor")
      (fields (field (name "TOLERANCE") "1%") (field (name "POWER") "62.5mW"))
      (libsource (lib "Green Team Twente") (part "RES_GENERIC"))
    )
    (comp (ref "R34")
      (value "75")
      (footprint "RES_SM1206_YAGEORC_N")
      (description "GTT Standard 1206 Resistor")
      (fields (field (name "TOLERANCE") "1%") (field (name "POWER") "250mW"))
      (libsource (lib "Green Team Twente") (part "RES_GENERIC"))
    )
    (comp (ref "R35")
      (value "3kR")
      (footprint "FP0402")
      (description "GTT Standard 0402 Resistor")
      (fields (field (name "TOLERANCE") "1%") (field (name "POWER") "62.5mW"))
      (libsource (lib "Green Team Twente") (part "RES_GENERIC"))
    )
    (comp (ref "R36")
      (value "2kR")
      (footprint "FP0402")
      (description "GTT Standard 0402 Resistor")
      (fields (field (name "TOLERANCE") "1%") (field (name "POWER") "62.5mW"))
      (libsource (lib "Green Team Twente") (part "RES_GENERIC"))
    )
    (comp (ref "R37")
      (value "3.3kR")
      (footprint "FP0402")
      (description "GTT Standard 0402 Resistor")
      (fields (field (name "TOLERANCE") "1%") (field (name "POWER") "62.5mW"))
      (libsource (lib "Green Team Twente") (part "RES_GENERIC"))
    )
    (comp (ref "R38")
      (value "3.3kR")
      (footprint "FP0402")
      (description "GTT Standard 0402 Resistor")
      (fields (field (name "TOLERANCE") "1%") (field (name "POWER") "62.5mW"))
      (libsource (lib "Green Team Twente") (part "RES_GENERIC"))
    )
    (comp (ref "R39")
      (value "75")
      (footprint "RES_SM1206_YAGEORC_N")
      (description "GTT Standard 1206 Resistor")
      (fields (field (name "TOLERANCE") "1%") (field (name "POWER") "250mW"))
      (libsource (lib "Green Team Twente") (part "RES_GENERIC"))
    )
    (comp (ref "R40")
      (value "3.3R")
      (footprint "FP0402")
      (description "GTT Standard 0402 Resistor")
      (fields (field (name "TOLERANCE") "1%") (field (name "POWER") "62.5mW"))
      (libsource (lib "Green Team Twente") (part "RES_GENERIC"))
    )
    (comp (ref "R41")
      (value "3kR")
      (footprint "FP0402")
      (description "GTT Standard 0402 Resistor")
      (fields (field (name "TOLERANCE") "1%") (field (name "POWER") "62.5mW"))
      (libsource (lib "Green Team Twente") (part "RES_GENERIC"))
    )
    (comp (ref "R42")
      (value "2kR")
      (footprint "FP0402")
      (description "GTT Standard 0402 Resistor")
      (fields (field (name "TOLERANCE") "1%") (field (name "POWER") "62.5mW"))
      (libsource (lib "Green Team Twente") (part "RES_GENERIC"))
    )
    (comp (ref "R43")
      (value "75")
      (footprint "RES_SM1206_YAGEORC_N")
      (description "GTT Standard 1206 Resistor")
      (fields (field (name "TOLERANCE") "1%") (field (name "POWER") "250mW"))
      (libsource (lib "Green Team Twente") (part "RES_GENERIC"))
    )
    (comp (ref "R44")
      (value "6.8kR")
      (footprint "FP0402")
      (description "GTT Standard 0402 Resistor")
      (fields (field (name "TOLERANCE") "1%") (field (name "POWER") "62.5mW"))
      (libsource (lib "Green Team Twente") (part "RES_GENERIC"))
    )
    (comp (ref "R45")
      (value "75")
      (footprint "RES_SM1206_YAGEORC_N")
      (description "GTT Standard 1206 Resistor")
      (fields (field (name "TOLERANCE") "1%") (field (name "POWER") "250mW"))
      (libsource (lib "Green Team Twente") (part "RES_GENERIC"))
    )
    (comp (ref "R46")
      (value "3kR")
      (footprint "FP0402")
      (description "GTT Standard 0402 Resistor")
      (fields (field (name "TOLERANCE") "1%") (field (name "POWER") "62.5mW"))
      (libsource (lib "Green Team Twente") (part "RES_GENERIC"))
    )
    (comp (ref "R47")
      (value "2kR")
      (footprint "FP0402")
      (description "GTT Standard 0402 Resistor")
      (fields (field (name "TOLERANCE") "1%") (field (name "POWER") "62.5mW"))
      (libsource (lib "Green Team Twente") (part "RES_GENERIC"))
    )
    (comp (ref "R48")
      (value "3.3R")
      (footprint "FP0402")
      (description "GTT Standard 0402 Resistor")
      (fields (field (name "TOLERANCE") "1%") (field (name "POWER") "62.5mW"))
      (libsource (lib "Green Team Twente") (part "RES_GENERIC"))
    )
    (comp (ref "R49")
      (value "3.3kR")
      (footprint "FP0402")
      (description "GTT Standard 0402 Resistor")
      (fields (field (name "TOLERANCE") "1%") (field (name "POWER") "62.5mW"))
      (libsource (lib "Green Team Twente") (part "RES_GENERIC"))
    )
    (comp (ref "R50")
      (value "3.3kR")
      (footprint "FP0402")
      (description "GTT Standard 0402 Resistor")
      (fields (field (name "TOLERANCE") "1%") (field (name "POWER") "62.5mW"))
      (libsource (lib "Green Team Twente") (part "RES_GENERIC"))
    )
    (comp (ref "R51")
      (value "75")
      (footprint "RES_SM1206_YAGEORC_N")
      (description "GTT Standard 1206 Resistor")
      (fields (field (name "TOLERANCE") "1%") (field (name "POWER") "250mW"))
      (libsource (lib "Green Team Twente") (part "RES_GENERIC"))
    )
    (comp (ref "R52")
      (value "3kR")
      (footprint "FP0402")
      (description "GTT Standard 0402 Resistor")
      (fields (field (name "TOLERANCE") "1%") (field (name "POWER") "62.5mW"))
      (libsource (lib "Green Team Twente") (part "RES_GENERIC"))
    )
    (comp (ref "R53")
      (value "2kR")
      (footprint "FP0402")
      (description "GTT Standard 0402 Resistor")
      (fields (field (name "TOLERANCE") "1%") (field (name "POWER") "62.5mW"))
      (libsource (lib "Green Team Twente") (part "RES_GENERIC"))
    )
    (comp (ref "R54")
      (value "75")
      (footprint "RES_SM1206_YAGEORC_N")
      (description "GTT Standard 1206 Resistor")
      (fields (field (name "TOLERANCE") "1%") (field (name "POWER") "250mW"))
      (libsource (lib "Green Team Twente") (part "RES_GENERIC"))
    )
    (comp (ref "R55")
      (value "6.8kR")
      (footprint "FP0402")
      (description "GTT Standard 0402 Resistor")
      (fields (field (name "TOLERANCE") "1%") (field (name "POWER") "62.5mW"))
      (libsource (lib "Green Team Twente") (part "RES_GENERIC"))
    )
    (comp (ref "R56")
      (value "3.3R")
      (footprint "FP0402")
      (description "GTT Standard 0402 Resistor")
      (fields (field (name "TOLERANCE") "1%") (field (name "POWER") "62.5mW"))
      (libsource (lib "Green Team Twente") (part "RES_GENERIC"))
    )
    (comp (ref "R57")
      (value "3kR")
      (footprint "FP0402")
      (description "GTT Standard 0402 Resistor")
      (fields (field (name "TOLERANCE") "1%") (field (name "POWER") "62.5mW"))
      (libsource (lib "Green Team Twente") (part "RES_GENERIC"))
    )
    (comp (ref "R58")
      (value "2kR")
      (footprint "FP0402")
      (description "GTT Standard 0402 Resistor")
      (fields (field (name "TOLERANCE") "1%") (field (name "POWER") "62.5mW"))
      (libsource (lib "Green Team Twente") (part "RES_GENERIC"))
    )
    (comp (ref "R59")
      (value "3.3kR")
      (footprint "FP0402")
      (description "GTT Standard 0402 Resistor")
      (fields (field (name "TOLERANCE") "1%") (field (name "POWER") "62.5mW"))
      (libsource (lib "Green Team Twente") (part "RES_GENERIC"))
    )
    (comp (ref "R60")
      (value "3.3kR")
      (footprint "FP0402")
      (description "GTT Standard 0402 Resistor")
      (fields (field (name "TOLERANCE") "1%") (field (name "POWER") "62.5mW"))
      (libsource (lib "Green Team Twente") (part "RES_GENERIC"))
    )
    (comp (ref "R61")
      (value "75")
      (footprint "RES_SM1206_YAGEORC_N")
      (description "GTT Standard 1206 Resistor")
      (fields (field (name "TOLERANCE") "1%") (field (name "POWER") "250mW"))
      (libsource (lib "Green Team Twente") (part "RES_GENERIC"))
    )
    (comp (ref "R62")
      (value "3kR")
      (footprint "FP0402")
      (description "GTT Standard 0402 Resistor")
      (fields (field (name "TOLERANCE") "1%") (field (name "POWER") "62.5mW"))
      (libsource (lib "Green Team Twente") (part "RES_GENERIC"))
    )
    (comp (ref "R63")
      (value "2kR")
      (footprint "FP0402")
      (description "GTT Standard 0402 Resistor")
      (fields (field (name "TOLERANCE") "1%") (field (name "POWER") "62.5mW"))
      (libsource (lib "Green Team Twente") (part "RES_GENERIC"))
    )
    (comp (ref "R64")
      (value "6.8kR")
      (footprint "FP0402")
      (description "GTT Standard 0402 Resistor")
      (fields (field (name "TOLERANCE") "1%") (field (name "POWER") "62.5mW"))
      (libsource (lib "Green Team Twente") (part "RES_GENERIC"))
    )
    (comp (ref "R65")
      (value "3kR")
      (footprint "FP0402")
      (description "GTT Standard 0402 Resistor")
      (fields (field (name "TOLERANCE") "1%") (field (name "POWER") "62.5mW"))
      (libsource (lib "Green Team Twente") (part "RES_GENERIC"))
    )
    (comp (ref "R66")
      (value "2kR")
      (footprint "FP0402")
      (description "GTT Standard 0402 Resistor")
      (fields (field (name "TOLERANCE") "1%") (field (name "POWER") "62.5mW"))
      (libsource (lib "Green Team Twente") (part "RES_GENERIC"))
    )
    (comp (ref "R67")
      (value "3.3kR")
      (footprint "FP0402")
      (description "GTT Standard 0402 Resistor")
      (fields (field (name "TOLERANCE") "1%") (field (name "POWER") "62.5mW"))
      (libsource (lib "Green Team Twente") (part "RES_GENERIC"))
    )
    (comp (ref "R68")
      (value "3.3kR")
      (footprint "FP0402")
      (description "GTT Standard 0402 Resistor")
      (fields (field (name "TOLERANCE") "1%") (field (name "POWER") "62.5mW"))
      (libsource (lib "Green Team Twente") (part "RES_GENERIC"))
    )
    (comp (ref "R69")
      (value "3kR")
      (footprint "FP0402")
      (description "GTT Standard 0402 Resistor")
      (fields (field (name "TOLERANCE") "1%") (field (name "POWER") "62.5mW"))
      (libsource (lib "Green Team Twente") (part "RES_GENERIC"))
    )
    (comp (ref "R70")
      (value "2kR")
      (footprint "FP0402")
      (description "GTT Standard 0402 Resistor")
      (fields (field (name "TOLERANCE") "1%") (field (name "POWER") "62.5mW"))
      (libsource (lib "Green Team Twente") (part "RES_GENERIC"))
    )
    (comp (ref "R71")
      (value "3kR")
      (footprint "FP0402")
      (description "GTT Standard 0402 Resistor")
      (fields (field (name "TOLERANCE") "1%") (field (name "POWER") "62.5mW"))
      (libsource (lib "Green Team Twente") (part "RES_GENERIC"))
    )
    (comp (ref "R72")
      (value "2kR")
      (footprint "FP0402")
      (description "GTT Standard 0402 Resistor")
      (fields (field (name "TOLERANCE") "1%") (field (name "POWER") "62.5mW"))
      (libsource (lib "Green Team Twente") (part "RES_GENERIC"))
    )
    (comp (ref "R73")
      (value "75")
      (footprint "RES_SM1206_YAGEORC_N")
      (description "GTT Standard 1206 Resistor")
      (fields (field (name "TOLERANCE") "1%") (field (name "POWER") "250mW"))
      (libsource (lib "Green Team Twente") (part "RES_GENERIC"))
    )
    (comp (ref "R80")
      (value "75")
      (footprint "RES_SM1206_YAGEORC_N")
      (description "GTT Standard 1206 Resistor")
      (fields (field (name "TOLERANCE") "1%") (field (name "POWER") "250mW"))
      (libsource (lib "Green Team Twente") (part "RES_GENERIC"))
    )
    (comp (ref "R81")
      (value "75")
      (footprint "RES_SM1206_YAGEORC_N")
      (description "GTT Standard 1206 Resistor")
      (fields (field (name "TOLERANCE") "1%") (field (name "POWER") "250mW"))
      (libsource (lib "Green Team Twente") (part "RES_GENERIC"))
    )
    (comp (ref "R82")
      (value "75")
      (footprint "RES_SM1206_YAGEORC_N")
      (description "GTT Standard 1206 Resistor")
      (fields (field (name "TOLERANCE") "1%") (field (name "POWER") "250mW"))
      (libsource (lib "Green Team Twente") (part "RES_GENERIC"))
    )
    (comp (ref "R83")
      (value "75")
      (footprint "RES_SM1206_YAGEORC_N")
      (description "GTT Standard 1206 Resistor")
      (fields (field (name "TOLERANCE") "1%") (field (name "POWER") "250mW"))
      (libsource (lib "Green Team Twente") (part "RES_GENERIC"))
    )
    (comp (ref "R84")
      (value "75")
      (footprint "RES_SM1206_YAGEORC_N")
      (description "GTT Standard 1206 Resistor")
      (fields (field (name "TOLERANCE") "1%") (field (name "POWER") "250mW"))
      (libsource (lib "Green Team Twente") (part "RES_GENERIC"))
    )
    (comp (ref "R85")
      (value "75")
      (footprint "RES_SM1206_YAGEORC_N")
      (description "GTT Standard 1206 Resistor")
      (fields (field (name "TOLERANCE") "1%") (field (name "POWER") "250mW"))
      (libsource (lib "Green Team Twente") (part "RES_GENERIC"))
    )
    (comp (ref "R86")
      (value "75")
      (footprint "RES_SM1206_YAGEORC_N")
      (description "GTT Standard 1206 Resistor")
      (fields (field (name "TOLERANCE") "1%") (field (name "POWER") "250mW"))
      (libsource (lib "Green Team Twente") (part "RES_GENERIC"))
    )
    (comp (ref "R87")
      (value "75")
      (footprint "RES_SM1206_YAGEORC_N")
      (description "GTT Standard 1206 Resistor")
      (fields (field (name "TOLERANCE") "1%") (field (name "POWER") "250mW"))
      (libsource (lib "Green Team Twente") (part "RES_GENERIC"))
    )
    (comp (ref "R88")
      (value "75")
      (footprint "RES_SM1206_YAGEORC_N")
      (description "GTT Standard 1206 Resistor")
      (fields (field (name "TOLERANCE") "1%") (field (name "POWER") "250mW"))
      (libsource (lib "Green Team Twente") (part "RES_GENERIC"))
    )
    (comp (ref "R89")
      (value "75")
      (footprint "RES_SM1206_YAGEORC_N")
      (description "GTT Standard 1206 Resistor")
      (fields (field (name "TOLERANCE") "1%") (field (name "POWER") "250mW"))
      (libsource (lib "Green Team Twente") (part "RES_GENERIC"))
    )
    (comp (ref "R90")
      (value "75")
      (footprint "RES_SM1206_YAGEORC_N")
      (description "GTT Standard 1206 Resistor")
      (fields (field (name "TOLERANCE") "1%") (field (name "POWER") "250mW"))
      (libsource (lib "Green Team Twente") (part "RES_GENERIC"))
    )
    (comp (ref "R91")
      (value "75")
      (footprint "RES_SM1206_YAGEORC_N")
      (description "GTT Standard 1206 Resistor")
      (fields (field (name "TOLERANCE") "1%") (field (name "POWER") "250mW"))
      (libsource (lib "Green Team Twente") (part "RES_GENERIC"))
    )
    (comp (ref "R92")
      (value "75")
      (footprint "RES_SM1206_YAGEORC_N")
      (description "GTT Standard 1206 Resistor")
      (fields (field (name "TOLERANCE") "1%") (field (name "POWER") "250mW"))
      (libsource (lib "Green Team Twente") (part "RES_GENERIC"))
    )
    (comp (ref "R93")
      (value "10R")
      (footprint "RES_SM1206_YAGEORC_N")
      (description "GTT Standard 1206 Resistor")
      (fields (field (name "TOLERANCE") "1%") (field (name "POWER") "250mW"))
      (libsource (lib "Green Team Twente") (part "RES_GENERIC"))
    )
    (comp (ref "TP1")
      (value "GTT_ProbeerPunt")
      (footprint "GTT_ProbeerPuntFP")
      (libsource (lib "Green Team Twente") (part "Test Point"))
    )
    (comp (ref "TP2")
      (value "GTT_ProbeerPunt")
      (footprint "GTT_ProbeerPuntFP")
      (libsource (lib "Green Team Twente") (part "Test Point"))
    )
    (comp (ref "TP3")
      (value "GTT_ProbeerPunt")
      (footprint "GTT_ProbeerPuntFP")
      (libsource (lib "Green Team Twente") (part "Test Point"))
    )
  )
  (nets
    (net (code "1") (name "/CB_1") (class "Default")
      (node (ref "IC1") (pin "36") (pinfunction "CB_1_36") (pintype "passive"))
      (node (ref "R91") (pin "2") (pinfunction "2_2") (pintype "passive"))
      (node (ref "R92") (pin "2") (pinfunction "2_2") (pintype "passive"))
    )
    (net (code "2") (name "/CB_2") (class "Default")
      (node (ref "IC1") (pin "34") (pinfunction "CB_2_34") (pintype "passive"))
      (node (ref "R89") (pin "2") (pinfunction "2_2") (pintype "passive"))
      (node (ref "R90") (pin "2") (pinfunction "2_2") (pintype "passive"))
    )
    (net (code "3") (name "/CB_2:1_C") (class "Default")
      (node (ref "IC1") (pin "35") (pinfunction "CB_2:1_C_35") (pintype "passive"))
      (node (ref "R56") (pin "1") (pinfunction "1_1") (pintype "passive"))
    )
    (net (code "4") (name "/CB_3") (class "Default")
      (node (ref "IC1") (pin "31") (pinfunction "CB_3_31") (pintype "passive"))
      (node (ref "R87") (pin "2") (pinfunction "2_2") (pintype "passive"))
      (node (ref "R88") (pin "2") (pinfunction "2_2") (pintype "passive"))
    )
    (net (code "5") (name "/CB_4") (class "Default")
      (node (ref "IC1") (pin "29") (pinfunction "CB_4_29") (pintype "passive"))
      (node (ref "R85") (pin "2") (pinfunction "2_2") (pintype "passive"))
      (node (ref "R86") (pin "2") (pinfunction "2_2") (pintype "passive"))
    )
    (net (code "6") (name "/CB_4:3_C") (class "Default")
      (node (ref "IC1") (pin "30") (pinfunction "CB_4:3_C_30") (pintype "passive"))
      (node (ref "R48") (pin "1") (pinfunction "1_1") (pintype "passive"))
    )
    (net (code "7") (name "/CB_5") (class "Default")
      (node (ref "IC1") (pin "26") (pinfunction "CB_5_26") (pintype "passive"))
      (node (ref "R83") (pin "2") (pinfunction "2_2") (pintype "passive"))
      (node (ref "R84") (pin "2") (pinfunction "2_2") (pintype "passive"))
    )
    (net (code "8") (name "/CB_6") (class "Default")
      (node (ref "IC1") (pin "24") (pinfunction "CB_6_24") (pintype "passive"))
      (node (ref "R81") (pin "2") (pinfunction "2_2") (pintype "passive"))
      (node (ref "R82") (pin "2") (pinfunction "2_2") (pintype "passive"))
    )
    (net (code "9") (name "/CB_6:5_C") (class "Default")
      (node (ref "IC1") (pin "25") (pinfunction "CB_6:5_C_25") (pintype "passive"))
      (node (ref "R40") (pin "1") (pinfunction "1_1") (pintype "passive"))
    )
    (net (code "10") (name "/CB_7") (class "Default")
      (node (ref "IC1") (pin "21") (pinfunction "CB_7_21") (pintype "passive"))
      (node (ref "R73") (pin "2") (pinfunction "2_2") (pintype "passive"))
      (node (ref "R80") (pin "2") (pinfunction "2_2") (pintype "passive"))
    )
    (net (code "11") (name "/CB_8") (class "Default")
      (node (ref "IC1") (pin "19") (pinfunction "CB_8_19") (pintype "passive"))
      (node (ref "R54") (pin "2") (pinfunction "2_2") (pintype "passive"))
      (node (ref "R61") (pin "2") (pinfunction "2_2") (pintype "passive"))
    )
    (net (code "12") (name "/CB_8:7_C") (class "Default")
      (node (ref "D4") (pin "2") (pinfunction "A_2") (pintype "passive"))
      (node (ref "IC1") (pin "20") (pinfunction "CB_8:7_C_20") (pintype "passive"))
      (node (ref "R32") (pin "1") (pinfunction "1_1") (pintype "passive"))
    )
    (net (code "13") (name "/CB_9") (class "Default")
      (node (ref "IC1") (pin "16") (pinfunction "CB_9_16") (pintype "passive"))
      (node (ref "R45") (pin "2") (pinfunction "2_2") (pintype "passive"))
      (node (ref "R51") (pin "2") (pinfunction "2_2") (pintype "passive"))
    )
    (net (code "14") (name "/CB_10") (class "Default")
      (node (ref "IC1") (pin "14") (pinfunction "CB_10_14") (pintype "passive"))
      (node (ref "R39") (pin "2") (pinfunction "2_2") (pintype "passive"))
      (node (ref "R43") (pin "2") (pinfunction "2_2") (pintype "passive"))
    )
    (net (code "15") (name "/CB_10:9_C") (class "Default")
      (node (ref "D5") (pin "2") (pinfunction "A_2") (pintype "passive"))
      (node (ref "IC1") (pin "15") (pinfunction "CB_10:9_C_15") (pintype "passive"))
      (node (ref "R23") (pin "1") (pinfunction "1_1") (pintype "passive"))
    )
    (net (code "16") (name "/CB_11") (class "Default")
      (node (ref "IC1") (pin "11") (pinfunction "CB_11_11") (pintype "passive"))
      (node (ref "R29") (pin "2") (pinfunction "2_2") (pintype "passive"))
      (node (ref "R34") (pin "2") (pinfunction "2_2") (pintype "passive"))
    )
    (net (code "17") (name "/CB_12") (class "Default")
      (node (ref "D1") (pin "2") (pinfunction "A_2") (pintype "passive"))
      (node (ref "IC1") (pin "9") (pinfunction "CB_12_9") (pintype "passive"))
      (node (ref "R21") (pin "2") (pinfunction "2_2") (pintype "passive"))
      (node (ref "R26") (pin "2") (pinfunction "2_2") (pintype "passive"))
    )
    (net (code "18") (name "/CB_12:11_C") (class "Default")
      (node (ref "IC1") (pin "10") (pinfunction "CB_12:11_C_10") (pintype "passive"))
      (node (ref "R15") (pin "1") (pinfunction "1_1") (pintype "passive"))
    )
    (net (code "19") (name "/CB_13") (class "Default")
      (node (ref "IC1") (pin "6") (pinfunction "CB_13_6") (pintype "passive"))
      (node (ref "R12") (pin "2") (pinfunction "2_2") (pintype "passive"))
      (node (ref "R18") (pin "2") (pinfunction "2_2") (pintype "passive"))
    )
    (net (code "20") (name "/CB_14") (class "Default")
      (node (ref "D6") (pin "2") (pinfunction "A_2") (pintype "passive"))
      (node (ref "IC1") (pin "4") (pinfunction "CB_14_4") (pintype "passive"))
      (node (ref "R10") (pin "2") (pinfunction "2_2") (pintype "passive"))
      (node (ref "R4") (pin "2") (pinfunction "2_2") (pintype "passive"))
    )
    (net (code "21") (name "/CB_14:13_C") (class "Default")
      (node (ref "IC1") (pin "5") (pinfunction "CB_14:13C_5") (pintype "passive"))
      (node (ref "R7") (pin "1") (pinfunction "1_1") (pintype "passive"))
    )
    (net (code "22") (name "/CELL1") (class "Default")
      (node (ref "C73") (pin "2") (pinfunction "2_2") (pintype "passive"))
      (node (ref "R56") (pin "2") (pinfunction "2_2") (pintype "passive"))
      (node (ref "R69") (pin "2") (pinfunction "2_2") (pintype "passive"))
    )
    (net (code "23") (name "/CELL2") (class "Default")
      (node (ref "C67") (pin "2") (pinfunction "2_2") (pintype "passive"))
      (node (ref "R65") (pin "2") (pinfunction "2_2") (pintype "passive"))
      (node (ref "R87") (pin "1") (pinfunction "1_1") (pintype "passive"))
      (node (ref "R88") (pin "1") (pinfunction "1_1") (pintype "passive"))
      (node (ref "R89") (pin "1") (pinfunction "1_1") (pintype "passive"))
      (node (ref "R90") (pin "1") (pinfunction "1_1") (pintype "passive"))
    )
    (net (code "24") (name "/CELL3") (class "Default")
      (node (ref "C63") (pin "2") (pinfunction "2_2") (pintype "passive"))
      (node (ref "R48") (pin "2") (pinfunction "2_2") (pintype "passive"))
      (node (ref "R62") (pin "2") (pinfunction "2_2") (pintype "passive"))
    )
    (net (code "25") (name "/CELL4") (class "Default")
      (node (ref "C57") (pin "2") (pinfunction "2_2") (pintype "passive"))
      (node (ref "R57") (pin "2") (pinfunction "2_2") (pintype "passive"))
      (node (ref "R83") (pin "1") (pinfunction "1_1") (pintype "passive"))
      (node (ref "R84") (pin "1") (pinfunction "1_1") (pintype "passive"))
      (node (ref "R85") (pin "1") (pinfunction "1_1") (pintype "passive"))
      (node (ref "R86") (pin "1") (pinfunction "1_1") (pintype "passive"))
    )
    (net (code "26") (name "/CELL5") (class "Default")
      (node (ref "C53") (pin "2") (pinfunction "2_2") (pintype "passive"))
      (node (ref "R40") (pin "2") (pinfunction "2_2") (pintype "passive"))
      (node (ref "R52") (pin "2") (pinfunction "2_2") (pintype "passive"))
    )
    (net (code "27") (name "/CELL6") (class "Default")
      (node (ref "C47") (pin "2") (pinfunction "2_2") (pintype "passive"))
      (node (ref "R46") (pin "2") (pinfunction "2_2") (pintype "passive"))
      (node (ref "R73") (pin "1") (pinfunction "1_1") (pintype "passive"))
      (node (ref "R80") (pin "1") (pinfunction "1_1") (pintype "passive"))
      (node (ref "R81") (pin "1") (pinfunction "1_1") (pintype "passive"))
      (node (ref "R82") (pin "1") (pinfunction "1_1") (pintype "passive"))
    )
    (net (code "28") (name "/CELL7") (class "Default")
      (node (ref "C43") (pin "2") (pinfunction "2_2") (pintype "passive"))
      (node (ref "R32") (pin "2") (pinfunction "2_2") (pintype "passive"))
      (node (ref "R41") (pin "2") (pinfunction "2_2") (pintype "passive"))
    )
    (net (code "29") (name "/CELL8") (class "Default")
      (node (ref "C37") (pin "2") (pinfunction "2_2") (pintype "passive"))
      (node (ref "R35") (pin "2") (pinfunction "2_2") (pintype "passive"))
      (node (ref "R45") (pin "1") (pinfunction "1_1") (pintype "passive"))
      (node (ref "R51") (pin "1") (pinfunction "1_1") (pintype "passive"))
      (node (ref "R54") (pin "1") (pinfunction "1_1") (pintype "passive"))
      (node (ref "R61") (pin "1") (pinfunction "1_1") (pintype "passive"))
    )
    (net (code "30") (name "/CELL9") (class "Default")
      (node (ref "C33") (pin "2") (pinfunction "2_2") (pintype "passive"))
      (node (ref "R23") (pin "2") (pinfunction "2_2") (pintype "passive"))
      (node (ref "R30") (pin "2") (pinfunction "2_2") (pintype "passive"))
    )
    (net (code "31") (name "/CELL10") (class "Default")
      (node (ref "C27") (pin "2") (pinfunction "2_2") (pintype "passive"))
      (node (ref "R24") (pin "2") (pinfunction "2_2") (pintype "passive"))
      (node (ref "R29") (pin "1") (pinfunction "1_1") (pintype "passive"))
      (node (ref "R34") (pin "1") (pinfunction "1_1") (pintype "passive"))
      (node (ref "R39") (pin "1") (pinfunction "1_1") (pintype "passive"))
      (node (ref "R43") (pin "1") (pinfunction "1_1") (pintype "passive"))
    )
    (net (code "32") (name "/CELL11") (class "Default")
      (node (ref "C22") (pin "2") (pinfunction "2_2") (pintype "passive"))
      (node (ref "R15") (pin "2") (pinfunction "2_2") (pintype "passive"))
      (node (ref "R19") (pin "2") (pinfunction "2_2") (pintype "passive"))
    )
    (net (code "33") (name "/CELL12") (class "Default")
      (node (ref "C14") (pin "2") (pinfunction "2_2") (pintype "passive"))
      (node (ref "R12") (pin "1") (pinfunction "1_1") (pintype "passive"))
      (node (ref "R13") (pin "2") (pinfunction "2_2") (pintype "passive"))
      (node (ref "R18") (pin "1") (pinfunction "1_1") (pintype "passive"))
      (node (ref "R21") (pin "1") (pinfunction "1_1") (pintype "passive"))
      (node (ref "R26") (pin "1") (pinfunction "1_1") (pintype "passive"))
    )
    (net (code "34") (name "/CELL13") (class "Default")
      (node (ref "C8") (pin "2") (pinfunction "2_2") (pintype "passive"))
      (node (ref "R7") (pin "2") (pinfunction "2_2") (pintype "passive"))
      (node (ref "R8") (pin "2") (pinfunction "2_2") (pintype "passive"))
    )
    (net (code "35") (name "/CELL14") (class "Default")
      (node (ref "C2") (pin "2") (pinfunction "2_2") (pintype "passive"))
      (node (ref "R10") (pin "1") (pinfunction "1_1") (pintype "passive"))
      (node (ref "R2") (pin "2") (pinfunction "2_2") (pintype "passive"))
      (node (ref "R4") (pin "1") (pinfunction "1_1") (pintype "passive"))
    )
    (net (code "37") (name "/CELL_REF") (class "Default")
      (node (ref "C76") (pin "2") (pinfunction "2_2") (pintype "passive"))
      (node (ref "D7") (pin "2") (pinfunction "K_2") (pintype "passive"))
      (node (ref "D8") (pin "1") (pinfunction "A_1") (pintype "passive"))
      (node (ref "R71") (pin "2") (pinfunction "2_2") (pintype "passive"))
      (node (ref "R91") (pin "1") (pinfunction "1_1") (pintype "passive"))
      (node (ref "R92") (pin "1") (pinfunction "1_1") (pintype "passive"))
    )
    (net (code "38") (name "/CT_1") (class "Default")
      (node (ref "C69") (pin "1") (pinfunction "1_1") (pintype "passive"))
      (node (ref "C75") (pin "2") (pinfunction "2_2") (pintype "passive"))
      (node (ref "IC1") (pin "37") (pinfunction "CT_1_37") (pintype "passive"))
      (node (ref "R70") (pin "1") (pinfunction "1_1") (pintype "passive"))
    )
    (net (code "39") (name "/CT_2") (class "Default")
      (node (ref "C65") (pin "1") (pinfunction "1_1") (pintype "passive"))
      (node (ref "C69") (pin "2") (pinfunction "2_2") (pintype "passive"))
      (node (ref "IC1") (pin "33") (pinfunction "CT_2_33") (pintype "passive"))
      (node (ref "R66") (pin "1") (pinfunction "1_1") (pintype "passive"))
    )
    (net (code "40") (name "/CT_3") (class "Default")
      (node (ref "C59") (pin "1") (pinfunction "1_1") (pintype "passive"))
      (node (ref "C65") (pin "2") (pinfunction "2_2") (pintype "passive"))
      (node (ref "IC1") (pin "32") (pinfunction "CT_3_32") (pintype "passive"))
      (node (ref "R63") (pin "1") (pinfunction "1_1") (pintype "passive"))
    )
    (net (code "41") (name "/CT_4") (class "Default")
      (node (ref "C55") (pin "1") (pinfunction "1_1") (pintype "passive"))
      (node (ref "C59") (pin "2") (pinfunction "2_2") (pintype "passive"))
      (node (ref "IC1") (pin "28") (pinfunction "CT_4_28") (pintype "passive"))
      (node (ref "R58") (pin "1") (pinfunction "1_1") (pintype "passive"))
    )
    (net (code "42") (name "/CT_5") (class "Default")
      (node (ref "C49") (pin "1") (pinfunction "1_1") (pintype "passive"))
      (node (ref "C55") (pin "2") (pinfunction "2_2") (pintype "passive"))
      (node (ref "IC1") (pin "27") (pinfunction "CT_5_27") (pintype "passive"))
      (node (ref "R53") (pin "1") (pinfunction "1_1") (pintype "passive"))
    )
    (net (code "43") (name "/CT_6") (class "Default")
      (node (ref "C45") (pin "1") (pinfunction "1_1") (pintype "passive"))
      (node (ref "C49") (pin "2") (pinfunction "2_2") (pintype "passive"))
      (node (ref "IC1") (pin "23") (pinfunction "CT_6_23") (pintype "passive"))
      (node (ref "R47") (pin "1") (pinfunction "1_1") (pintype "passive"))
    )
    (net (code "44") (name "/CT_7") (class "Default")
      (node (ref "C39") (pin "1") (pinfunction "1_1") (pintype "passive"))
      (node (ref "C45") (pin "2") (pinfunction "2_2") (pintype "passive"))
      (node (ref "IC1") (pin "22") (pinfunction "CT_7_22") (pintype "passive"))
      (node (ref "R42") (pin "1") (pinfunction "1_1") (pintype "passive"))
    )
    (net (code "45") (name "/CT_8") (class "Default")
      (node (ref "C35") (pin "1") (pinfunction "1_1") (pintype "passive"))
      (node (ref "C39") (pin "2") (pinfunction "2_2") (pintype "passive"))
      (node (ref "IC1") (pin "18") (pinfunction "CT_8_18") (pintype "passive"))
      (node (ref "R36") (pin "1") (pinfunction "1_1") (pintype "passive"))
    )
    (net (code "46") (name "/CT_9") (class "Default")
      (node (ref "C29") (pin "1") (pinfunction "1_1") (pintype "passive"))
      (node (ref "C35") (pin "2") (pinfunction "2_2") (pintype "passive"))
      (node (ref "IC1") (pin "17") (pinfunction "CT_9_17") (pintype "passive"))
      (node (ref "R31") (pin "1") (pinfunction "1_1") (pintype "passive"))
    )
    (net (code "47") (name "/CT_10") (class "Default")
      (node (ref "C25") (pin "1") (pinfunction "1_1") (pintype "passive"))
      (node (ref "C29") (pin "2") (pinfunction "2_2") (pintype "passive"))
      (node (ref "IC1") (pin "13") (pinfunction "CT_10_13") (pintype "passive"))
      (node (ref "R25") (pin "1") (pinfunction "1_1") (pintype "passive"))
    )
    (net (code "48") (name "/CT_11") (class "Default")
      (node (ref "C16") (pin "1") (pinfunction "1_1") (pintype "passive"))
      (node (ref "C25") (pin "2") (pinfunction "2_2") (pintype "passive"))
      (node (ref "IC1") (pin "12") (pinfunction "CT_11_12") (pintype "passive"))
      (node (ref "R20") (pin "1") (pinfunction "1_1") (pintype "passive"))
    )
    (net (code "49") (name "/CT_12") (class "Default")
      (node (ref "C10") (pin "1") (pinfunction "1_1") (pintype "passive"))
      (node (ref "C16") (pin "2") (pinfunction "2_2") (pintype "passive"))
      (node (ref "IC1") (pin "8") (pinfunction "CT_12_8") (pintype "passive"))
      (node (ref "R14") (pin "1") (pinfunction "1_1") (pintype "passive"))
    )
    (net (code "50") (name "/CT_13") (class "Default")
      (node (ref "C10") (pin "2") (pinfunction "2_2") (pintype "passive"))
      (node (ref "C4") (pin "1") (pinfunction "1_1") (pintype "passive"))
      (node (ref "IC1") (pin "7") (pinfunction "CT_13_7") (pintype "passive"))
      (node (ref "R9") (pin "1") (pinfunction "1_1") (pintype "passive"))
    )
    (net (code "51") (name "/CT_14") (class "Default")
      (node (ref "C4") (pin "2") (pinfunction "2_2") (pintype "passive"))
      (node (ref "D3") (pin "1") (pinfunction "K1_1") (pintype "passive"))
      (node (ref "IC1") (pin "3") (pinfunction "CT_14_3") (pintype "passive"))
      (node (ref "R3") (pin "1") (pinfunction "1_1") (pintype "passive"))
    )
    (net (code "52") (name "/CT_REF") (class "Default")
      (node (ref "C75") (pin "1") (pinfunction "1_1") (pintype "passive"))
      (node (ref "C95") (pin "2") (pinfunction "2_2") (pintype "passive"))
      (node (ref "IC1") (pin "38") (pinfunction "CT_REF_38") (pintype "passive"))
      (node (ref "R72") (pin "1") (pinfunction "1_1") (pintype "passive"))
    )
    (net (code "53") (name "/GPIO0") (class "Default")
      (node (ref "C7") (pin "2") (pinfunction "2_2") (pintype "passive"))
      (node (ref "IC1") (pin "49") (pinfunction "GPIO0_49") (pintype "passive"))
      (node (ref "R6") (pin "1") (pinfunction "1_1") (pintype "passive"))
    )
    (net (code "54") (name "/GPIO1") (class "Default")
      (node (ref "C19") (pin "2") (pinfunction "2_2") (pintype "passive"))
      (node (ref "IC1") (pin "50") (pinfunction "GPIO1_50") (pintype "passive"))
      (node (ref "R17") (pin "1") (pinfunction "1_1") (pintype "passive"))
    )
    (net (code "55") (name "/GPIO2") (class "Default")
      (node (ref "C32") (pin "2") (pinfunction "2_2") (pintype "passive"))
      (node (ref "IC1") (pin "51") (pinfunction "GPIO2_51") (pintype "passive"))
      (node (ref "R28") (pin "1") (pinfunction "1_1") (pintype "passive"))
    )
    (net (code "56") (name "/GPIO3") (class "Default")
      (node (ref "C42") (pin "2") (pinfunction "2_2") (pintype "passive"))
      (node (ref "IC1") (pin "52") (pinfunction "GPIO3_52") (pintype "passive"))
      (node (ref "R38") (pin "1") (pinfunction "1_1") (pintype "passive"))
    )
    (net (code "57") (name "/GPIO4") (class "Default")
      (node (ref "C52") (pin "2") (pinfunction "2_2") (pintype "passive"))
      (node (ref "IC1") (pin "53") (pinfunction "GPIO4_53") (pintype "passive"))
      (node (ref "R50") (pin "1") (pinfunction "1_1") (pintype "passive"))
    )
    (net (code "58") (name "/GPIO5") (class "Default")
      (node (ref "C62") (pin "2") (pinfunction "2_2") (pintype "passive"))
      (node (ref "IC1") (pin "54") (pinfunction "GPIO5_54") (pintype "passive"))
      (node (ref "R60") (pin "1") (pinfunction "1_1") (pintype "passive"))
    )
    (net (code "59") (name "/GPIO6") (class "Default")
      (node (ref "C72") (pin "2") (pinfunction "2_2") (pintype "passive"))
      (node (ref "IC1") (pin "55") (pinfunction "GPIO6_55") (pintype "passive"))
      (node (ref "R68") (pin "1") (pinfunction "1_1") (pintype "passive"))
    )
    (net (code "60") (name "/Isense+") (class "Default")
      (node (ref "IC1") (pin "56") (pinfunction "ISENSE+_56") (pintype "passive"))
    )
    (net (code "61") (name "/Isense-") (class "Default")
      (node (ref "IC1") (pin "57") (pinfunction "ISENSE-_57") (pintype "passive"))
    )
    (net (code "62") (name "/NTC0") (class "Default")
      (node (ref "C5") (pin "2") (pinfunction "2_2") (pintype "passive"))
      (node (ref "R1") (pin "2") (pinfunction "2_2") (pintype "passive"))
      (node (ref "R5") (pin "2") (pinfunction "2_2") (pintype "passive"))
    )
    (net (code "63") (name "/NTC1") (class "Default")
      (node (ref "C17") (pin "2") (pinfunction "2_2") (pintype "passive"))
      (node (ref "R11") (pin "2") (pinfunction "2_2") (pintype "passive"))
      (node (ref "R16") (pin "2") (pinfunction "2_2") (pintype "passive"))
    )
    (net (code "64") (name "/NTC2") (class "Default")
      (node (ref "C30") (pin "2") (pinfunction "2_2") (pintype "passive"))
      (node (ref "R22") (pin "2") (pinfunction "2_2") (pintype "passive"))
      (node (ref "R27") (pin "2") (pinfunction "2_2") (pintype "passive"))
    )
    (net (code "65") (name "/NTC3") (class "Default")
      (node (ref "C40") (pin "2") (pinfunction "2_2") (pintype "passive"))
      (node (ref "R33") (pin "2") (pinfunction "2_2") (pintype "passive"))
      (node (ref "R37") (pin "2") (pinfunction "2_2") (pintype "passive"))
    )
    (net (code "66") (name "/NTC4") (class "Default")
      (node (ref "C50") (pin "2") (pinfunction "2_2") (pintype "passive"))
      (node (ref "R44") (pin "2") (pinfunction "2_2") (pintype "passive"))
      (node (ref "R49") (pin "2") (pinfunction "2_2") (pintype "passive"))
    )
    (net (code "67") (name "/NTC5") (class "Default")
      (node (ref "C60") (pin "2") (pinfunction "2_2") (pintype "passive"))
      (node (ref "R55") (pin "2") (pinfunction "2_2") (pintype "passive"))
      (node (ref "R59") (pin "2") (pinfunction "2_2") (pintype "passive"))
    )
    (net (code "68") (name "/NTC6") (class "Default")
      (node (ref "C70") (pin "2") (pinfunction "2_2") (pintype "passive"))
      (node (ref "R64") (pin "2") (pinfunction "2_2") (pintype "passive"))
      (node (ref "R67") (pin "2") (pinfunction "2_2") (pintype "passive"))
    )
    (net (code "70") (name "/TPL_IN+") (class "Default")
      (node (ref "IC1") (pin "47") (pinfunction "SI/RDTX_IN+_47") (pintype "passive"))
    )
    (net (code "71") (name "/TPL_IN-") (class "Default")
      (node (ref "IC1") (pin "46") (pinfunction "SCLK/RDXT_IN-_46") (pintype "passive"))
    )
    (net (code "72") (name "/TPL_OUT+") (class "Default")
      (node (ref "IC1") (pin "48") (pinfunction "RDTX_OUT+_48") (pintype "passive"))
    )
    (net (code "73") (name "/TPL_OUT-") (class "Default")
      (node (ref "IC1") (pin "45") (pinfunction "RDTX_OUT-_45") (pintype "passive"))
    )
    (net (code "74") (name "/VBAT") (class "Default")
      (node (ref "C78") (pin "2") (pinfunction "2_2") (pintype "passive"))
      (node (ref "R93") (pin "1") (pinfunction "1_1") (pintype "passive"))
    )
    (net (code "75") (name "/VCOM") (class "Default")
      (node (ref "C1") (pin "2") (pinfunction "2_2") (pintype "passive"))
      (node (ref "C11") (pin "2") (pinfunction "2_2") (pintype "passive"))
      (node (ref "C20") (pin "2") (pinfunction "2_2") (pintype "passive"))
      (node (ref "C21") (pin "2") (pinfunction "2_2") (pintype "passive"))
      (node (ref "C26") (pin "2") (pinfunction "2_2") (pintype "passive"))
      (node (ref "C36") (pin "2") (pinfunction "2_2") (pintype "passive"))
      (node (ref "C46") (pin "2") (pinfunction "2_2") (pintype "passive"))
      (node (ref "C56") (pin "2") (pinfunction "2_2") (pintype "passive"))
      (node (ref "C66") (pin "2") (pinfunction "2_2") (pintype "passive"))
      (node (ref "IC1") (pin "43") (pinfunction "VCOM_43") (pintype "passive"))
      (node (ref "R1") (pin "1") (pinfunction "1_1") (pintype "passive"))
      (node (ref "R11") (pin "1") (pinfunction "1_1") (pintype "passive"))
      (node (ref "R22") (pin "1") (pinfunction "1_1") (pintype "passive"))
      (node (ref "R33") (pin "1") (pinfunction "1_1") (pintype "passive"))
      (node (ref "R44") (pin "1") (pinfunction "1_1") (pintype "passive"))
      (node (ref "R55") (pin "1") (pinfunction "1_1") (pintype "passive"))
      (node (ref "R64") (pin "1") (pinfunction "1_1") (pintype "passive"))
      (node (ref "TP3") (pin "1") (pinfunction "1_1") (pintype "passive"))
    )
    (net (code "76") (name "/VPWR") (class "Default")
      (node (ref "C12") (pin "2") (pinfunction "2_2") (pintype "passive"))
      (node (ref "C13") (pin "2") (pinfunction "2_2") (pintype "passive"))
      (node (ref "D1") (pin "1") (pinfunction "K_1") (pintype "passive"))
      (node (ref "D2") (pin "1") (pinfunction "K_1") (pintype "passive"))
      (node (ref "D3") (pin "2") (pinfunction "K2_2") (pintype "passive"))
      (node (ref "D4") (pin "1") (pinfunction "K_1") (pintype "passive"))
      (node (ref "D5") (pin "1") (pinfunction "K_1") (pintype "passive"))
      (node (ref "D6") (pin "1") (pinfunction "K_1") (pintype "passive"))
      (node (ref "IC1") (pin "1") (pinfunction "VPWR2_1") (pintype "passive"))
      (node (ref "IC1") (pin "2") (pinfunction "VPWR1_2") (pintype "passive"))
      (node (ref "R93") (pin "2") (pinfunction "2_2") (pintype "passive"))
      (node (ref "TP2") (pin "1") (pinfunction "1_1") (pintype "passive"))
    )
    (net (code "77") (name "GND") (class "Default")
      (node (ref "C12") (pin "1") (pinfunction "1_1") (pintype "passive"))
      (node (ref "C13") (pin "1") (pinfunction "1_1") (pintype "passive"))
      (node (ref "C14") (pin "1") (pinfunction "1_1") (pintype "passive"))
      (node (ref "C15") (pin "1") (pinfunction "1_1") (pintype "passive"))
      (node (ref "C17") (pin "1") (pinfunction "1_1") (pintype "passive"))
      (node (ref "C18") (pin "1") (pinfunction "1_1") (pintype "passive"))
      (node (ref "C19") (pin "1") (pinfunction "1_1") (pintype "passive"))
      (node (ref "C2") (pin "1") (pinfunction "1_1") (pintype "passive"))
      (node (ref "C20") (pin "1") (pinfunction "1_1") (pintype "passive"))
      (node (ref "C21") (pin "1") (pinfunction "1_1") (pintype "passive"))
      (node (ref "C22") (pin "1") (pinfunction "1_1") (pintype "passive"))
      (node (ref "C23") (pin "1") (pinfunction "1_1") (pintype "passive"))
      (node (ref "C24") (pin "1") (pinfunction "1_1") (pintype "passive"))
      (node (ref "C27") (pin "1") (pinfunction "1_1") (pintype "passive"))
      (node (ref "C28") (pin "1") (pinfunction "1_1") (pintype "passive"))
      (node (ref "C3") (pin "1") (pinfunction "1_1") (pintype "passive"))
      (node (ref "C30") (pin "1") (pinfunction "1_1") (pintype "passive"))
      (node (ref "C31") (pin "1") (pinfunction "1_1") (pintype "passive"))
      (node (ref "C32") (pin "1") (pinfunction "1_1") (pintype "passive"))
      (node (ref "C33") (pin "1") (pinfunction "1_1") (pintype "passive"))
      (node (ref "C34") (pin "1") (pinfunction "1_1") (pintype "passive"))
      (node (ref "C37") (pin "1") (pinfunction "1_1") (pintype "passive"))
      (node (ref "C38") (pin "1") (pinfunction "1_1") (pintype "passive"))
      (node (ref "C40") (pin "1") (pinfunction "1_1") (pintype "passive"))
      (node (ref "C41") (pin "1") (pinfunction "1_1") (pintype "passive"))
      (node (ref "C42") (pin "1") (pinfunction "1_1") (pintype "passive"))
      (node (ref "C43") (pin "1") (pinfunction "1_1") (pintype "passive"))
      (node (ref "C44") (pin "1") (pinfunction "1_1") (pintype "passive"))
      (node (ref "C47") (pin "1") (pinfunction "1_1") (pintype "passive"))
      (node (ref "C48") (pin "1") (pinfunction "1_1") (pintype "passive"))
      (node (ref "C5") (pin "1") (pinfunction "1_1") (pintype "passive"))
      (node (ref "C50") (pin "1") (pinfunction "1_1") (pintype "passive"))
      (node (ref "C51") (pin "1") (pinfunction "1_1") (pintype "passive"))
      (node (ref "C52") (pin "1") (pinfunction "1_1") (pintype "passive"))
      (node (ref "C53") (pin "1") (pinfunction "1_1") (pintype "passive"))
      (node (ref "C54") (pin "1") (pinfunction "1_1") (pintype "passive"))
      (node (ref "C57") (pin "1") (pinfunction "1_1") (pintype "passive"))
      (node (ref "C58") (pin "1") (pinfunction "1_1") (pintype "passive"))
      (node (ref "C6") (pin "1") (pinfunction "1_1") (pintype "passive"))
      (node (ref "C60") (pin "1") (pinfunction "1_1") (pintype "passive"))
      (node (ref "C61") (pin "1") (pinfunction "1_1") (pintype "passive"))
      (node (ref "C62") (pin "1") (pinfunction "1_1") (pintype "passive"))
      (node (ref "C63") (pin "1") (pinfunction "1_1") (pintype "passive"))
      (node (ref "C64") (pin "1") (pinfunction "1_1") (pintype "passive"))
      (node (ref "C67") (pin "1") (pinfunction "1_1") (pintype "passive"))
      (node (ref "C68") (pin "1") (pinfunction "1_1") (pintype "passive"))
      (node (ref "C7") (pin "1") (pinfunction "1_1") (pintype "passive"))
      (node (ref "C70") (pin "1") (pinfunction "1_1") (pintype "passive"))
      (node (ref "C71") (pin "1") (pinfunction "1_1") (pintype "passive"))
      (node (ref "C72") (pin "1") (pinfunction "1_1") (pintype "passive"))
      (node (ref "C73") (pin "1") (pinfunction "1_1") (pintype "passive"))
      (node (ref "C74") (pin "1") (pinfunction "1_1") (pintype "passive"))
      (node (ref "C76") (pin "1") (pinfunction "1_1") (pintype "passive"))
      (node (ref "C77") (pin "1") (pinfunction "1_1") (pintype "passive"))
      (node (ref "C78") (pin "1") (pinfunction "1_1") (pintype "passive"))
      (node (ref "C8") (pin "1") (pinfunction "1_1") (pintype "passive"))
      (node (ref "C9") (pin "1") (pinfunction "1_1") (pintype "passive"))
      (node (ref "C95") (pin "1") (pinfunction "1_1") (pintype "passive"))
      (node (ref "D2") (pin "2") (pinfunction "A_2") (pintype "passive"))
      (node (ref "D7") (pin "1") (pinfunction "A_1") (pintype "passive"))
      (node (ref "D8") (pin "2") (pinfunction "K_2") (pintype "passive"))
      (node (ref "IC1") (pin "39") (pinfunction "SPI_COM_EN_39") (pintype "passive"))
      (node (ref "IC1") (pin "41") (pinfunction "CSB_41") (pintype "passive"))
      (node (ref "IC1") (pin "44") (pinfunction "CGND_44") (pintype "passive"))
      (node (ref "IC1") (pin "58") (pinfunction "AGND_58") (pintype "passive"))
      (node (ref "IC1") (pin "59") (pinfunction "DGND_59") (pintype "passive"))
      (node (ref "IC1") (pin "63") (pinfunction "RESET_63") (pintype "passive"))
      (node (ref "IC1") (pin "64") (pinfunction "GNDREF_64") (pintype "passive"))
      (node (ref "IC1") (pin "65") (pinfunction "GNDFLAG_65") (pintype "passive"))
      (node (ref "TP1") (pin "1") (pinfunction "1_1") (pintype "passive"))
    )
    (net (code "78") (name "Net-(C1-Pad1)") (class "Default")
      (node (ref "C1") (pin "1") (pinfunction "1_1") (pintype "passive"))
      (node (ref "C6") (pin "2") (pinfunction "2_2") (pintype "passive"))
      (node (ref "R5") (pin "1") (pinfunction "1_1") (pintype "passive"))
      (node (ref "R6") (pin "2") (pinfunction "2_2") (pintype "passive"))
    )
    (net (code "79") (name "Net-(C3-Pad2)") (class "Default")
      (node (ref "C3") (pin "2") (pinfunction "2_2") (pintype "passive"))
      (node (ref "R2") (pin "1") (pinfunction "1_1") (pintype "passive"))
      (node (ref "R3") (pin "2") (pinfunction "2_2") (pintype "passive"))
    )
    (net (code "80") (name "Net-(C9-Pad2)") (class "Default")
      (node (ref "C9") (pin "2") (pinfunction "2_2") (pintype "passive"))
      (node (ref "R8") (pin "1") (pinfunction "1_1") (pintype "passive"))
      (node (ref "R9") (pin "2") (pinfunction "2_2") (pintype "passive"))
    )
    (net (code "81") (name "Net-(C11-Pad1)") (class "Default")
      (node (ref "C11") (pin "1") (pinfunction "1_1") (pintype "passive"))
      (node (ref "C18") (pin "2") (pinfunction "2_2") (pintype "passive"))
      (node (ref "R16") (pin "1") (pinfunction "1_1") (pintype "passive"))
      (node (ref "R17") (pin "2") (pinfunction "2_2") (pintype "passive"))
    )
    (net (code "82") (name "Net-(C15-Pad2)") (class "Default")
      (node (ref "C15") (pin "2") (pinfunction "2_2") (pintype "passive"))
      (node (ref "R13") (pin "1") (pinfunction "1_1") (pintype "passive"))
      (node (ref "R14") (pin "2") (pinfunction "2_2") (pintype "passive"))
    )
    (net (code "83") (name "Net-(C23-Pad2)") (class "Default")
      (node (ref "C23") (pin "2") (pinfunction "2_2") (pintype "passive"))
      (node (ref "R19") (pin "1") (pinfunction "1_1") (pintype "passive"))
      (node (ref "R20") (pin "2") (pinfunction "2_2") (pintype "passive"))
    )
    (net (code "84") (name "Net-(C26-Pad1)") (class "Default")
      (node (ref "C26") (pin "1") (pinfunction "1_1") (pintype "passive"))
      (node (ref "C31") (pin "2") (pinfunction "2_2") (pintype "passive"))
      (node (ref "R27") (pin "1") (pinfunction "1_1") (pintype "passive"))
      (node (ref "R28") (pin "2") (pinfunction "2_2") (pintype "passive"))
    )
    (net (code "85") (name "Net-(C28-Pad2)") (class "Default")
      (node (ref "C28") (pin "2") (pinfunction "2_2") (pintype "passive"))
      (node (ref "R24") (pin "1") (pinfunction "1_1") (pintype "passive"))
      (node (ref "R25") (pin "2") (pinfunction "2_2") (pintype "passive"))
    )
    (net (code "86") (name "Net-(C34-Pad2)") (class "Default")
      (node (ref "C34") (pin "2") (pinfunction "2_2") (pintype "passive"))
      (node (ref "R30") (pin "1") (pinfunction "1_1") (pintype "passive"))
      (node (ref "R31") (pin "2") (pinfunction "2_2") (pintype "passive"))
    )
    (net (code "87") (name "Net-(C36-Pad1)") (class "Default")
      (node (ref "C36") (pin "1") (pinfunction "1_1") (pintype "passive"))
      (node (ref "C41") (pin "2") (pinfunction "2_2") (pintype "passive"))
      (node (ref "R37") (pin "1") (pinfunction "1_1") (pintype "passive"))
      (node (ref "R38") (pin "2") (pinfunction "2_2") (pintype "passive"))
    )
    (net (code "88") (name "Net-(C38-Pad2)") (class "Default")
      (node (ref "C38") (pin "2") (pinfunction "2_2") (pintype "passive"))
      (node (ref "R35") (pin "1") (pinfunction "1_1") (pintype "passive"))
      (node (ref "R36") (pin "2") (pinfunction "2_2") (pintype "passive"))
    )
    (net (code "89") (name "Net-(C44-Pad2)") (class "Default")
      (node (ref "C44") (pin "2") (pinfunction "2_2") (pintype "passive"))
      (node (ref "R41") (pin "1") (pinfunction "1_1") (pintype "passive"))
      (node (ref "R42") (pin "2") (pinfunction "2_2") (pintype "passive"))
    )
    (net (code "90") (name "Net-(C46-Pad1)") (class "Default")
      (node (ref "C46") (pin "1") (pinfunction "1_1") (pintype "passive"))
      (node (ref "C51") (pin "2") (pinfunction "2_2") (pintype "passive"))
      (node (ref "R49") (pin "1") (pinfunction "1_1") (pintype "passive"))
      (node (ref "R50") (pin "2") (pinfunction "2_2") (pintype "passive"))
    )
    (net (code "91") (name "Net-(C48-Pad2)") (class "Default")
      (node (ref "C48") (pin "2") (pinfunction "2_2") (pintype "passive"))
      (node (ref "R46") (pin "1") (pinfunction "1_1") (pintype "passive"))
      (node (ref "R47") (pin "2") (pinfunction "2_2") (pintype "passive"))
    )
    (net (code "92") (name "Net-(C54-Pad2)") (class "Default")
      (node (ref "C54") (pin "2") (pinfunction "2_2") (pintype "passive"))
      (node (ref "R52") (pin "1") (pinfunction "1_1") (pintype "passive"))
      (node (ref "R53") (pin "2") (pinfunction "2_2") (pintype "passive"))
    )
    (net (code "93") (name "Net-(C56-Pad1)") (class "Default")
      (node (ref "C56") (pin "1") (pinfunction "1_1") (pintype "passive"))
      (node (ref "C61") (pin "2") (pinfunction "2_2") (pintype "passive"))
      (node (ref "R59") (pin "1") (pinfunction "1_1") (pintype "passive"))
      (node (ref "R60") (pin "2") (pinfunction "2_2") (pintype "passive"))
    )
    (net (code "94") (name "Net-(C58-Pad2)") (class "Default")
      (node (ref "C58") (pin "2") (pinfunction "2_2") (pintype "passive"))
      (node (ref "R57") (pin "1") (pinfunction "1_1") (pintype "passive"))
      (node (ref "R58") (pin "2") (pinfunction "2_2") (pintype "passive"))
    )
    (net (code "95") (name "Net-(C64-Pad2)") (class "Default")
      (node (ref "C64") (pin "2") (pinfunction "2_2") (pintype "passive"))
      (node (ref "R62") (pin "1") (pinfunction "1_1") (pintype "passive"))
      (node (ref "R63") (pin "2") (pinfunction "2_2") (pintype "passive"))
    )
    (net (code "96") (name "Net-(C66-Pad1)") (class "Default")
      (node (ref "C66") (pin "1") (pinfunction "1_1") (pintype "passive"))
      (node (ref "C71") (pin "2") (pinfunction "2_2") (pintype "passive"))
      (node (ref "R67") (pin "1") (pinfunction "1_1") (pintype "passive"))
      (node (ref "R68") (pin "2") (pinfunction "2_2") (pintype "passive"))
    )
    (net (code "97") (name "Net-(C68-Pad2)") (class "Default")
      (node (ref "C68") (pin "2") (pinfunction "2_2") (pintype "passive"))
      (node (ref "R65") (pin "1") (pinfunction "1_1") (pintype "passive"))
      (node (ref "R66") (pin "2") (pinfunction "2_2") (pintype "passive"))
    )
    (net (code "98") (name "Net-(C74-Pad2)") (class "Default")
      (node (ref "C74") (pin "2") (pinfunction "2_2") (pintype "passive"))
      (node (ref "R69") (pin "1") (pinfunction "1_1") (pintype "passive"))
      (node (ref "R70") (pin "2") (pinfunction "2_2") (pintype "passive"))
    )
    (net (code "99") (name "Net-(C77-Pad2)") (class "Default")
      (node (ref "C77") (pin "2") (pinfunction "2_2") (pintype "passive"))
      (node (ref "R71") (pin "1") (pinfunction "1_1") (pintype "passive"))
      (node (ref "R72") (pin "2") (pinfunction "2_2") (pintype "passive"))
    )
    (net (code "100") (name "Net-(IC1-VANA)") (class "Default")
      (node (ref "C24") (pin "2") (pinfunction "2_2") (pintype "passive"))
      (node (ref "IC1") (pin "60") (pinfunction "VANA_60") (pintype "passive"))
    )
    (net (code "101") (name "unconnected-(IC1-FAULT-Pad40)") (class "Default")
      (node (ref "IC1") (pin "40") (pinfunction "FAULT_40") (pintype "passive+no_connect"))
    )
    (net (code "102") (name "unconnected-(IC1-SCL-Pad61)") (class "Default")
      (node (ref "IC1") (pin "61") (pinfunction "SCL_61") (pintype "passive+no_connect"))
    )
    (net (code "103") (name "unconnected-(IC1-SDA-Pad62)") (class "Default")
      (node (ref "IC1") (pin "62") (pinfunction "SDA_62") (pintype "passive+no_connect"))
    )
    (net (code "104") (name "unconnected-(IC1-SO-Pad42)") (class "Default")
      (node (ref "IC1") (pin "42") (pinfunction "SO_42") (pintype "passive+no_connect"))
    )
  )
)
